# GTI_V5.net
KiCad netlist of a schematic drawn in Altium Designer
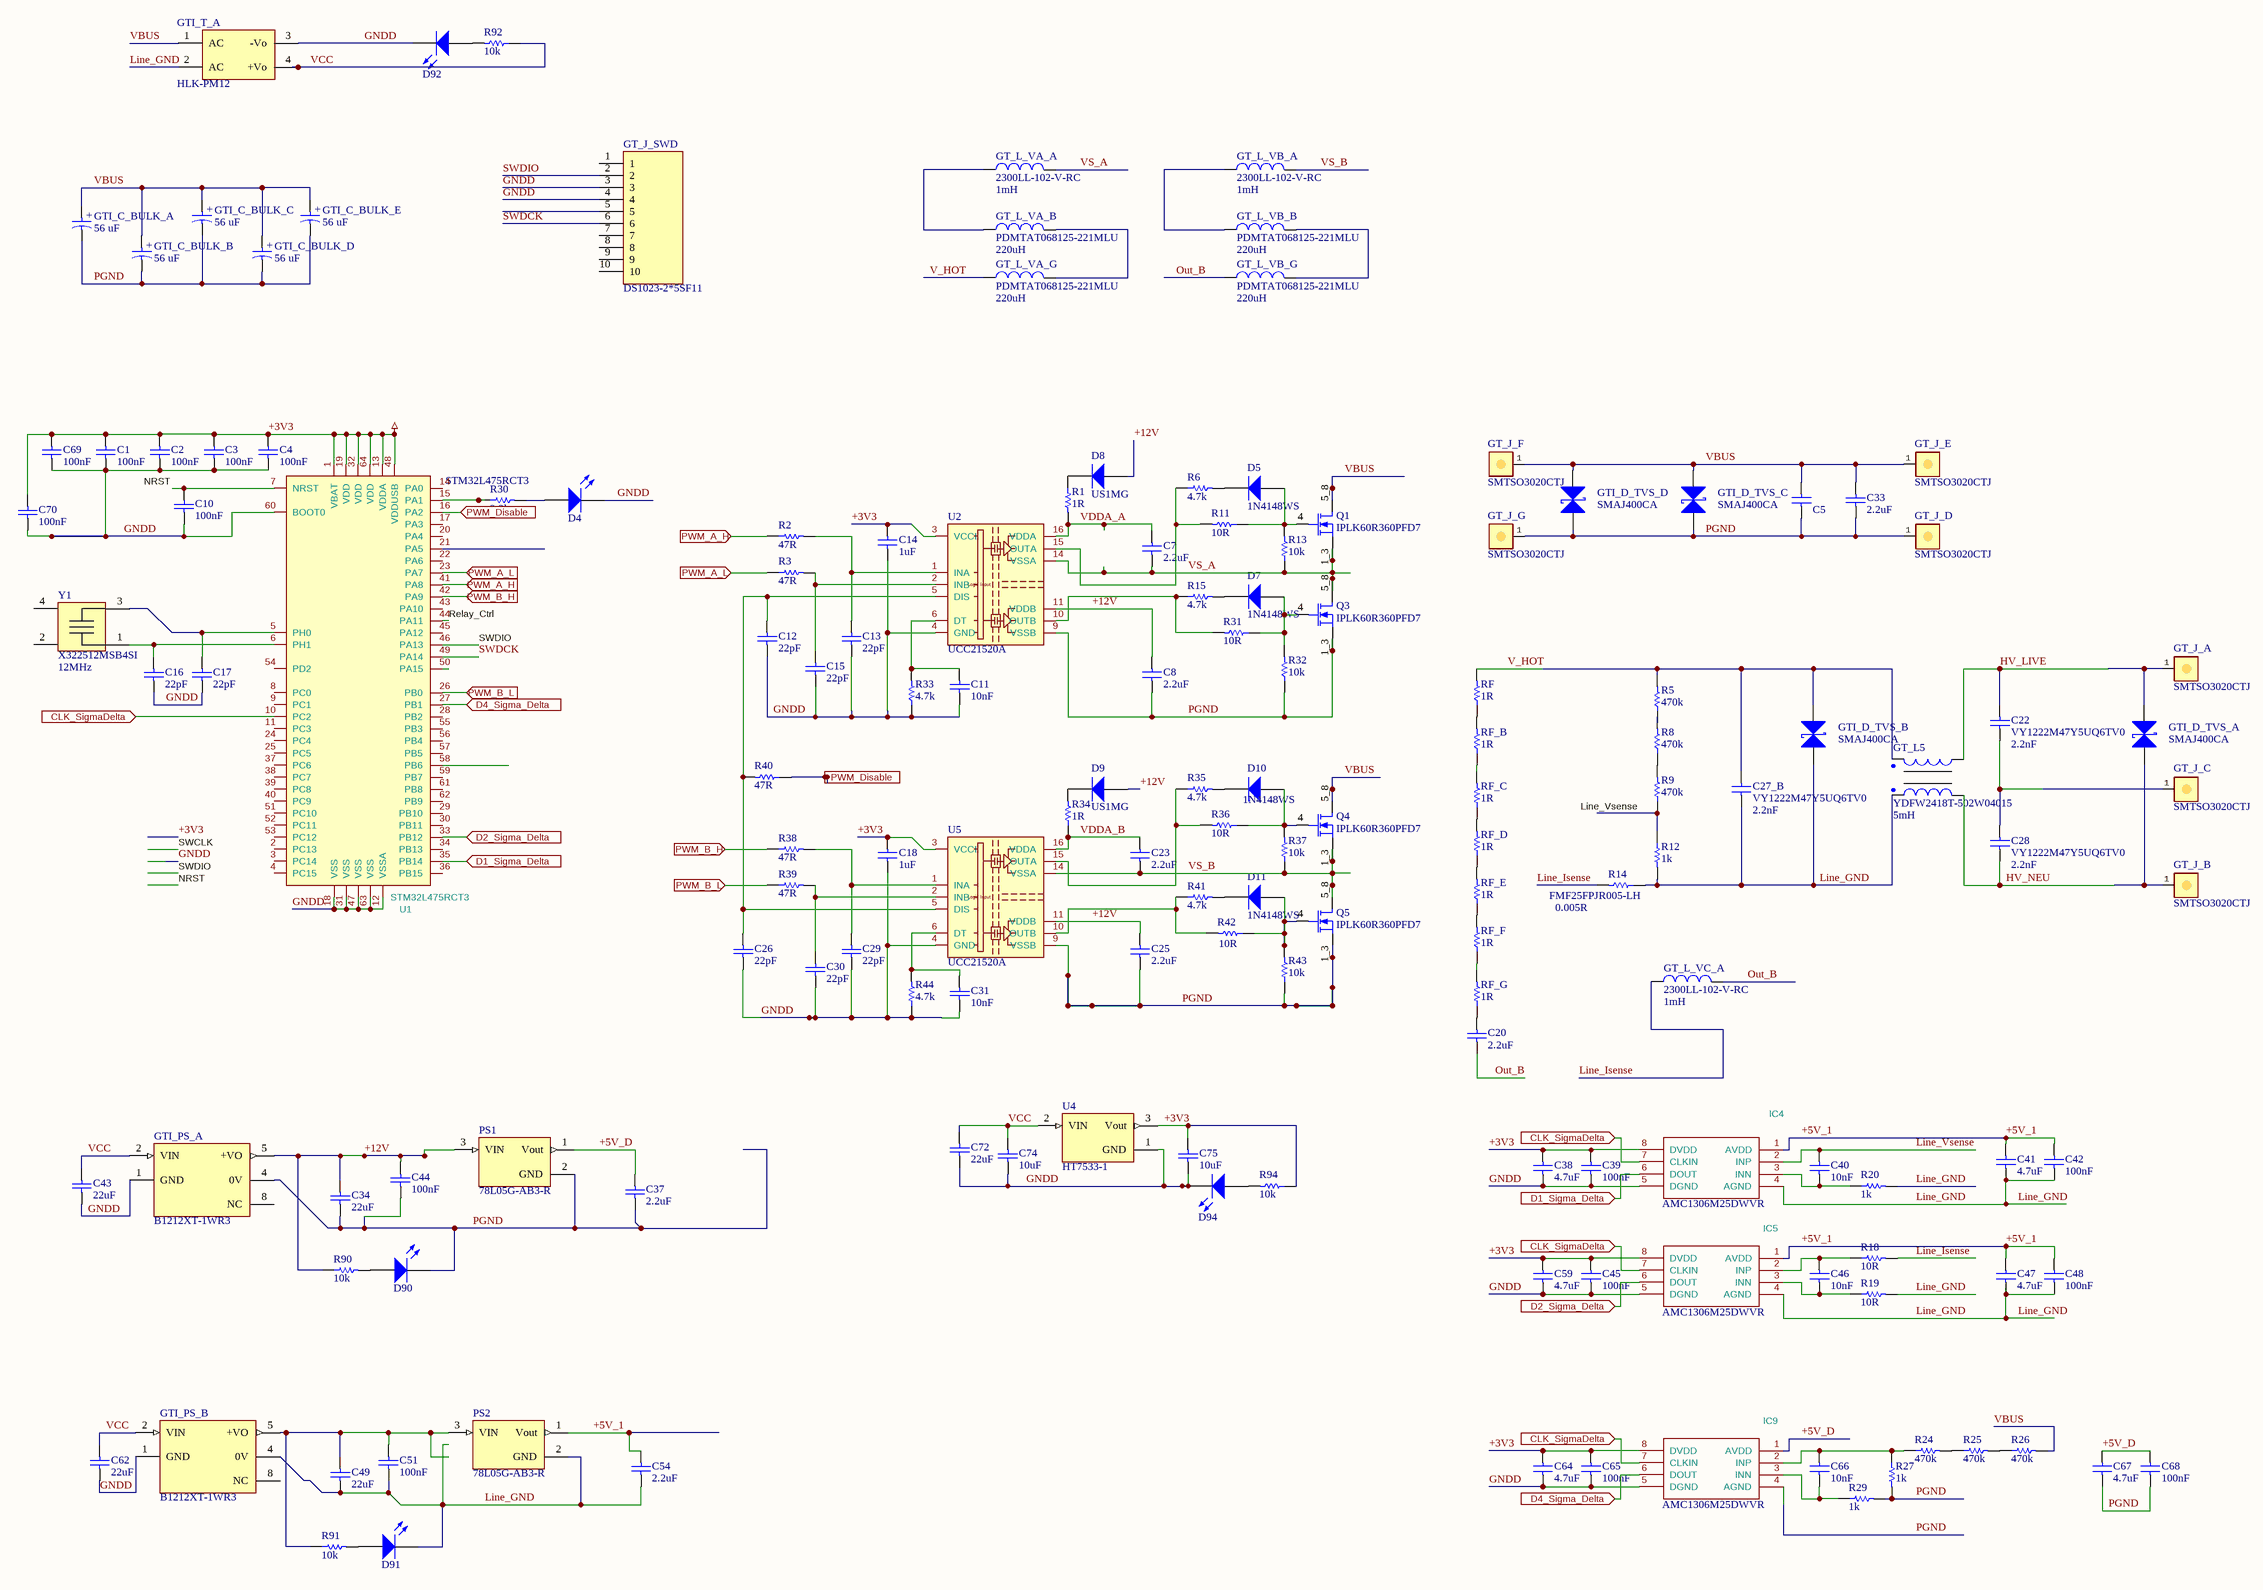
[diagram p0: GTI_V5.SchDoc]

(export (version "E")
  (design (tool "Eeschema 10.0.6"))
  (components
    (comp (ref "C1")
      (value "100nF")
      (footprint "C_0402")
      (description "C - CAPACITOR - MLCC - 100nF - 16V - 0402")
      (fields (field (name "LCSC PART #") "C1525") (field (name "Comment") "CL05B104KO5NNNC"))
      (libsource (lib "JLC_PCB") (part "CL05B104KO5NNNC"))
    )
    (comp (ref "C2")
      (value "100nF")
      (footprint "C_0402")
      (description "C - CAPACITOR - MLCC - 100nF - 16V - 0402")
      (fields (field (name "LCSC PART #") "C1525") (field (name "Comment") "CL05B104KO5NNNC"))
      (libsource (lib "JLC_PCB") (part "CL05B104KO5NNNC"))
    )
    (comp (ref "C3")
      (value "100nF")
      (footprint "C_0402")
      (description "C - CAPACITOR - MLCC - 100nF - 16V - 0402")
      (fields (field (name "LCSC PART #") "C1525") (field (name "Comment") "CL05B104KO5NNNC"))
      (libsource (lib "JLC_PCB") (part "CL05B104KO5NNNC"))
    )
    (comp (ref "C4")
      (value "100nF")
      (footprint "C_0402")
      (description "C - CAPACITOR - MLCC - 100nF - 16V - 0402")
      (fields (field (name "LCSC PART #") "C1525") (field (name "Comment") "CL05B104KO5NNNC"))
      (libsource (lib "JLC_PCB") (part "CL05B104KO5NNNC"))
    )
    (comp (ref "C5")
      (value "C5750X6S2W225KT000N")
      (footprint "C_2220")
      (description "C - CAPACITOR - MLCC - 2.2uF - 450V - 2020")
      (fields (field (name "LCSC PART #") "C445674"))
      (libsource (lib "JLC_PCB") (part "C5750X6S2W225KT000N"))
    )
    (comp (ref "C7")
      (value "2.2uF")
      (footprint "C_0603")
      (description "C - CAPACITOR - MLCC - 2.2uF - 16V - 0603")
      (fields (field (name "LCSC PART #") "C23630") (field (name "Comment") "CL10A225KO8NNNC"))
      (libsource (lib "JLC_PCB") (part "CL10A225KO8NNNC"))
    )
    (comp (ref "C8")
      (value "2.2uF")
      (footprint "C_0603")
      (description "C - CAPACITOR - MLCC - 2.2uF - 16V - 0603")
      (fields (field (name "LCSC PART #") "C23630") (field (name "Comment") "CL10A225KO8NNNC"))
      (libsource (lib "JLC_PCB") (part "CL10A225KO8NNNC"))
    )
    (comp (ref "C10")
      (value "100nF")
      (footprint "C_0402")
      (description "C - CAPACITOR - MLCC - 100nF - 16V - 0402")
      (fields (field (name "LCSC PART #") "C1525") (field (name "Comment") "CL05B104KO5NNNC"))
      (libsource (lib "JLC_PCB") (part "CL05B104KO5NNNC"))
    )
    (comp (ref "C11")
      (value "10nF")
      (footprint "C_0402")
      (description "C - CAPACITOR - MLCC - 10nF - 50V - 0402")
      (fields (field (name "LCSC PART #") "C15195") (field (name "Comment") "CL05B103KB5NNNC"))
      (libsource (lib "JLC_PCB") (part "CL05B103KB5NNNC"))
    )
    (comp (ref "C12")
      (value "22pF")
      (footprint "C_0402")
      (description "C - CAPACITOR - MLCC - 22pF - 50V - 0402")
      (fields (field (name "LCSC PART #") "C1555") (field (name "Comment") "0402CG220J500NT"))
      (libsource (lib "JLC_PCB") (part "0402CG220J500NT"))
    )
    (comp (ref "C13")
      (value "22pF")
      (footprint "C_0402")
      (description "C - CAPACITOR - MLCC - 22pF - 50V - 0402")
      (fields (field (name "LCSC PART #") "C1555") (field (name "Comment") "0402CG220J500NT"))
      (libsource (lib "JLC_PCB") (part "0402CG220J500NT"))
    )
    (comp (ref "C14")
      (value "1uF")
      (footprint "C_0402")
      (description "C - CAPACITOR - MLCC - 1uF - 25V - 0402")
      (fields (field (name "LCSC PART #") "C52923") (field (name "Comment") "CL05A105KA5NQNC"))
      (libsource (lib "JLC_PCB") (part "CL05A105KA5NQNC"))
    )
    (comp (ref "C15")
      (value "22pF")
      (footprint "C_0402")
      (description "C - CAPACITOR - MLCC - 22pF - 50V - 0402")
      (fields (field (name "LCSC PART #") "C1555") (field (name "Comment") "0402CG220J500NT"))
      (libsource (lib "JLC_PCB") (part "0402CG220J500NT"))
    )
    (comp (ref "C16")
      (value "22pF")
      (footprint "C_0402")
      (description "C - CAPACITOR - MLCC - 22pF - 50V - 0402")
      (fields (field (name "LCSC PART #") "C1555") (field (name "Comment") "0402CG220J500NT"))
      (libsource (lib "JLC_PCB") (part "0402CG220J500NT"))
    )
    (comp (ref "C17")
      (value "22pF")
      (footprint "C_0402")
      (description "C - CAPACITOR - MLCC - 22pF - 50V - 0402")
      (fields (field (name "LCSC PART #") "C1555") (field (name "Comment") "0402CG220J500NT"))
      (libsource (lib "JLC_PCB") (part "0402CG220J500NT"))
    )
    (comp (ref "C18")
      (value "1uF")
      (footprint "C_0402")
      (description "C - CAPACITOR - MLCC - 1uF - 25V - 0402")
      (fields (field (name "LCSC PART #") "C52923") (field (name "Comment") "CL05A105KA5NQNC"))
      (libsource (lib "JLC_PCB") (part "CL05A105KA5NQNC"))
    )
    (comp (ref "C20")
      (value "2.2uF")
      (footprint "C_FILM_D27.5")
      (description "C - CAPACITOR - FILM - 2.2uF - 630V - 10mm Plugin")
      (fields (field (name "LCSC PART #") "C5371183") (field (name "Comment") "KP225J2J2705"))
      (libsource (lib "JLC_PCB") (part "KP225J2J2705"))
    )
    (comp (ref "C22")
      (value "VY1222M47Y5UQ6TV0")
      (footprint "C_DISK_D10")
      (description "C - CAPACITOR - X/Y - 2.2nF - 1.5kV - 10mm Plugin")
      (fields (field (name "ALTIUM_VALUE") "2.2nF") (field (name "LCSC PART #") "C499511"))
      (libsource (lib "JLC_PCB") (part "VY1222M47Y5UQ6TV0"))
    )
    (comp (ref "C23")
      (value "2.2uF")
      (footprint "C_0603")
      (description "C - CAPACITOR - MLCC - 2.2uF - 16V - 0603")
      (fields (field (name "LCSC PART #") "C23630") (field (name "Comment") "CL10A225KO8NNNC"))
      (libsource (lib "JLC_PCB") (part "CL10A225KO8NNNC"))
    )
    (comp (ref "C25")
      (value "2.2uF")
      (footprint "C_0603")
      (description "C - CAPACITOR - MLCC - 2.2uF - 16V - 0603")
      (fields (field (name "LCSC PART #") "C23630") (field (name "Comment") "CL10A225KO8NNNC"))
      (libsource (lib "JLC_PCB") (part "CL10A225KO8NNNC"))
    )
    (comp (ref "C26")
      (value "22pF")
      (footprint "C_0402")
      (description "C - CAPACITOR - MLCC - 22pF - 50V - 0402")
      (fields (field (name "LCSC PART #") "C1555") (field (name "Comment") "0402CG220J500NT"))
      (libsource (lib "JLC_PCB") (part "0402CG220J500NT"))
    )
    (comp (ref "C27_B")
      (value "VY1222M47Y5UQ6TV0")
      (footprint "C_DISK_D10")
      (description "C - CAPACITOR - X/Y - 2.2nF - 1.5kV - 10mm Plugin")
      (fields (field (name "ALTIUM_VALUE") "2.2nF") (field (name "LCSC PART #") "C499511"))
      (libsource (lib "JLC_PCB") (part "VY1222M47Y5UQ6TV0"))
    )
    (comp (ref "C28")
      (value "VY1222M47Y5UQ6TV0")
      (footprint "C_DISK_D10")
      (description "C - CAPACITOR - X/Y - 2.2nF - 1.5kV - 10mm Plugin")
      (fields (field (name "ALTIUM_VALUE") "2.2nF") (field (name "LCSC PART #") "C499511"))
      (libsource (lib "JLC_PCB") (part "VY1222M47Y5UQ6TV0"))
    )
    (comp (ref "C29")
      (value "22pF")
      (footprint "C_0402")
      (description "C - CAPACITOR - MLCC - 22pF - 50V - 0402")
      (fields (field (name "LCSC PART #") "C1555") (field (name "Comment") "0402CG220J500NT"))
      (libsource (lib "JLC_PCB") (part "0402CG220J500NT"))
    )
    (comp (ref "C30")
      (value "22pF")
      (footprint "C_0402")
      (description "C - CAPACITOR - MLCC - 22pF - 50V - 0402")
      (fields (field (name "LCSC PART #") "C1555") (field (name "Comment") "0402CG220J500NT"))
      (libsource (lib "JLC_PCB") (part "0402CG220J500NT"))
    )
    (comp (ref "C31")
      (value "10nF")
      (footprint "C_0402")
      (description "C - CAPACITOR - MLCC - 10nF - 50V - 0402")
      (fields (field (name "LCSC PART #") "C15195") (field (name "Comment") "CL05B103KB5NNNC"))
      (libsource (lib "JLC_PCB") (part "CL05B103KB5NNNC"))
    )
    (comp (ref "C33")
      (value "2.2uF")
      (footprint "C_FILM_D27.5")
      (description "C - CAPACITOR - FILM - 2.2uF - 630V - 10mm Plugin")
      (fields (field (name "LCSC PART #") "C5371183") (field (name "Comment") "KP225J2J2705"))
      (libsource (lib "JLC_PCB") (part "KP225J2J2705"))
    )
    (comp (ref "C34")
      (value "22uF")
      (footprint "C_1206")
      (description "C - CAPACITOR - MLCC - 22uF - 25V - 1206")
      (fields (field (name "LCSC PART #") "C12891") (field (name "Comment") "CL31A226KAHNNNE"))
      (libsource (lib "JLC_PCB") (part "CL31A226KAHNNNE"))
    )
    (comp (ref "C37")
      (value "2.2uF")
      (footprint "C_0603")
      (description "C - CAPACITOR - MLCC - 2.2uF - 16V - 0603")
      (fields (field (name "LCSC PART #") "C23630") (field (name "Comment") "CL10A225KO8NNNC"))
      (libsource (lib "JLC_PCB") (part "CL10A225KO8NNNC"))
    )
    (comp (ref "C38")
      (value "4.7uF")
      (footprint "C_0402")
      (description "C - CAPACITOR - MLCC - 4.7uF - 10V - 0402")
      (fields (field (name "LCSC PART #") "C23733") (field (name "Comment") "CL05A475MP5NRNC"))
      (libsource (lib "JLC_PCB") (part "CL05A475MP5NRNC"))
    )
    (comp (ref "C39")
      (value "100nF")
      (footprint "C_0402")
      (description "C - CAPACITOR - MLCC - 100nF - 16V - 0402")
      (fields (field (name "LCSC PART #") "C1525") (field (name "Comment") "CL05B104KO5NNNC"))
      (libsource (lib "JLC_PCB") (part "CL05B104KO5NNNC"))
    )
    (comp (ref "C40")
      (value "10nF")
      (footprint "C_0402")
      (description "C - CAPACITOR - MLCC - 10nF - 50V - 0402")
      (fields (field (name "LCSC PART #") "C15195") (field (name "Comment") "CL05B103KB5NNNC"))
      (libsource (lib "JLC_PCB") (part "CL05B103KB5NNNC"))
    )
    (comp (ref "C41")
      (value "4.7uF")
      (footprint "C_0402")
      (description "C - CAPACITOR - MLCC - 4.7uF - 10V - 0402")
      (fields (field (name "LCSC PART #") "C23733") (field (name "Comment") "CL05A475MP5NRNC"))
      (libsource (lib "JLC_PCB") (part "CL05A475MP5NRNC"))
    )
    (comp (ref "C42")
      (value "100nF")
      (footprint "C_0402")
      (description "C - CAPACITOR - MLCC - 100nF - 16V - 0402")
      (fields (field (name "LCSC PART #") "C1525") (field (name "Comment") "CL05B104KO5NNNC"))
      (libsource (lib "JLC_PCB") (part "CL05B104KO5NNNC"))
    )
    (comp (ref "C43")
      (value "22uF")
      (footprint "C_1206")
      (description "C - CAPACITOR - MLCC - 22uF - 25V - 1206")
      (fields (field (name "LCSC PART #") "C12891") (field (name "Comment") "CL31A226KAHNNNE"))
      (libsource (lib "JLC_PCB") (part "CL31A226KAHNNNE"))
    )
    (comp (ref "C44")
      (value "100nF")
      (footprint "C_0603")
      (description "C - CAPACITOR - MLCC - 100nF - 50V - 0603")
      (fields (field (name "LCSC PART #") "C14663") (field (name "Comment") "CC0603KRX7R9BB104"))
      (libsource (lib "JLC_PCB") (part "CC0603KRX7R9BB104"))
    )
    (comp (ref "C45")
      (value "100nF")
      (footprint "C_0402")
      (description "C - CAPACITOR - MLCC - 100nF - 16V - 0402")
      (fields (field (name "LCSC PART #") "C1525") (field (name "Comment") "CL05B104KO5NNNC"))
      (libsource (lib "JLC_PCB") (part "CL05B104KO5NNNC"))
    )
    (comp (ref "C46")
      (value "10nF")
      (footprint "C_0402")
      (description "C - CAPACITOR - MLCC - 10nF - 50V - 0402")
      (fields (field (name "LCSC PART #") "C15195") (field (name "Comment") "CL05B103KB5NNNC"))
      (libsource (lib "JLC_PCB") (part "CL05B103KB5NNNC"))
    )
    (comp (ref "C47")
      (value "4.7uF")
      (footprint "C_0402")
      (description "C - CAPACITOR - MLCC - 4.7uF - 10V - 0402")
      (fields (field (name "LCSC PART #") "C23733") (field (name "Comment") "CL05A475MP5NRNC"))
      (libsource (lib "JLC_PCB") (part "CL05A475MP5NRNC"))
    )
    (comp (ref "C48")
      (value "100nF")
      (footprint "C_0402")
      (description "C - CAPACITOR - MLCC - 100nF - 16V - 0402")
      (fields (field (name "LCSC PART #") "C1525") (field (name "Comment") "CL05B104KO5NNNC"))
      (libsource (lib "JLC_PCB") (part "CL05B104KO5NNNC"))
    )
    (comp (ref "C49")
      (value "22uF")
      (footprint "C_1206")
      (description "C - CAPACITOR - MLCC - 22uF - 25V - 1206")
      (fields (field (name "LCSC PART #") "C12891") (field (name "Comment") "CL31A226KAHNNNE"))
      (libsource (lib "JLC_PCB") (part "CL31A226KAHNNNE"))
    )
    (comp (ref "C51")
      (value "100nF")
      (footprint "C_0603")
      (description "C - CAPACITOR - MLCC - 100nF - 50V - 0603")
      (fields (field (name "LCSC PART #") "C14663") (field (name "Comment") "CC0603KRX7R9BB104"))
      (libsource (lib "JLC_PCB") (part "CC0603KRX7R9BB104"))
    )
    (comp (ref "C54")
      (value "2.2uF")
      (footprint "C_0603")
      (description "C - CAPACITOR - MLCC - 2.2uF - 16V - 0603")
      (fields (field (name "LCSC PART #") "C23630") (field (name "Comment") "CL10A225KO8NNNC"))
      (libsource (lib "JLC_PCB") (part "CL10A225KO8NNNC"))
    )
    (comp (ref "C59")
      (value "4.7uF")
      (footprint "C_0402")
      (description "C - CAPACITOR - MLCC - 4.7uF - 10V - 0402")
      (fields (field (name "LCSC PART #") "C23733") (field (name "Comment") "CL05A475MP5NRNC"))
      (libsource (lib "JLC_PCB") (part "CL05A475MP5NRNC"))
    )
    (comp (ref "C62")
      (value "22uF")
      (footprint "C_1206")
      (description "C - CAPACITOR - MLCC - 22uF - 25V - 1206")
      (fields (field (name "LCSC PART #") "C12891") (field (name "Comment") "CL31A226KAHNNNE"))
      (libsource (lib "JLC_PCB") (part "CL31A226KAHNNNE"))
    )
    (comp (ref "C64")
      (value "4.7uF")
      (footprint "C_0402")
      (description "C - CAPACITOR - MLCC - 4.7uF - 10V - 0402")
      (fields (field (name "LCSC PART #") "C23733") (field (name "Comment") "CL05A475MP5NRNC"))
      (libsource (lib "JLC_PCB") (part "CL05A475MP5NRNC"))
    )
    (comp (ref "C65")
      (value "100nF")
      (footprint "C_0402")
      (description "C - CAPACITOR - MLCC - 100nF - 16V - 0402")
      (fields (field (name "LCSC PART #") "C1525") (field (name "Comment") "CL05B104KO5NNNC"))
      (libsource (lib "JLC_PCB") (part "CL05B104KO5NNNC"))
    )
    (comp (ref "C66")
      (value "10nF")
      (footprint "C_0402")
      (description "C - CAPACITOR - MLCC - 10nF - 50V - 0402")
      (fields (field (name "LCSC PART #") "C15195") (field (name "Comment") "CL05B103KB5NNNC"))
      (libsource (lib "JLC_PCB") (part "CL05B103KB5NNNC"))
    )
    (comp (ref "C67")
      (value "4.7uF")
      (footprint "C_0402")
      (description "C - CAPACITOR - MLCC - 4.7uF - 10V - 0402")
      (fields (field (name "LCSC PART #") "C23733") (field (name "Comment") "CL05A475MP5NRNC"))
      (libsource (lib "JLC_PCB") (part "CL05A475MP5NRNC"))
    )
    (comp (ref "C68")
      (value "100nF")
      (footprint "C_0402")
      (description "C - CAPACITOR - MLCC - 100nF - 16V - 0402")
      (fields (field (name "LCSC PART #") "C1525") (field (name "Comment") "CL05B104KO5NNNC"))
      (libsource (lib "JLC_PCB") (part "CL05B104KO5NNNC"))
    )
    (comp (ref "C69")
      (value "100nF")
      (footprint "C_0402")
      (description "C - CAPACITOR - MLCC - 100nF - 16V - 0402")
      (fields (field (name "LCSC PART #") "C1525") (field (name "Comment") "CL05B104KO5NNNC"))
      (libsource (lib "JLC_PCB") (part "CL05B104KO5NNNC"))
    )
    (comp (ref "C70")
      (value "100nF")
      (footprint "C_0402")
      (description "C - CAPACITOR - MLCC - 100nF - 16V - 0402")
      (fields (field (name "LCSC PART #") "C1525") (field (name "Comment") "CL05B104KO5NNNC"))
      (libsource (lib "JLC_PCB") (part "CL05B104KO5NNNC"))
    )
    (comp (ref "C72")
      (value "22uF")
      (footprint "C_1206")
      (description "C - CAPACITOR - MLCC - 22uF - 25V - 1206")
      (fields (field (name "LCSC PART #") "C12891") (field (name "Comment") "CL31A226KAHNNNE"))
      (libsource (lib "JLC_PCB") (part "CL31A226KAHNNNE"))
    )
    (comp (ref "C74")
      (value "10uF")
      (footprint "C_0603")
      (description "C - CAPACITOR - MLCC - 10uF - 25V - 0603")
      (fields (field (name "LCSC PART #") "C96446") (field (name "Comment") "CL10A106MA8NRNC"))
      (libsource (lib "JLC_PCB") (part "CL10A106MA8NRNC"))
    )
    (comp (ref "C75")
      (value "10uF")
      (footprint "C_0603")
      (description "C - CAPACITOR - MLCC - 10uF - 25V - 0603")
      (fields (field (name "LCSC PART #") "C96446") (field (name "Comment") "CL10A106MA8NRNC"))
      (libsource (lib "JLC_PCB") (part "CL10A106MA8NRNC"))
    )
    (comp (ref "D4")
      (value "KT-0603R")
      (footprint "D_0603")
      (description "D - LED - 0603 - Red")
      (fields (field (name "LCSC PART #") "C2286"))
      (libsource (lib "JLC_PCB") (part "KT-0603R"))
    )
    (comp (ref "D5")
      (value "1N4148WS")
      (footprint "SOD-323")
      (description "D - DIODE - FAST TRR - 100V - 150mA - 4ns")
      (fields (field (name "LCSC PART #") "C2128"))
      (libsource (lib "JLC_PCB") (part "1N4148WS"))
    )
    (comp (ref "D7")
      (value "1N4148WS")
      (footprint "SOD-323")
      (description "D - DIODE - FAST TRR - 100V - 150mA - 4ns")
      (fields (field (name "LCSC PART #") "C2128"))
      (libsource (lib "JLC_PCB") (part "1N4148WS"))
    )
    (comp (ref "D8")
      (value "US1MG")
      (footprint "DO-214AC")
      (description "D - DIODE - FAST TRR - 1KV - 1A")
      (fields (field (name "LCSC PART #") "C412437"))
      (libsource (lib "JLC_PCB") (part "US1MG"))
    )
    (comp (ref "D9")
      (value "US1MG")
      (footprint "DO-214AC")
      (description "D - DIODE - FAST TRR - 1KV - 1A")
      (fields (field (name "LCSC PART #") "C412437"))
      (libsource (lib "JLC_PCB") (part "US1MG"))
    )
    (comp (ref "D10")
      (value "1N4148WS")
      (footprint "SOD-323")
      (description "D - DIODE - FAST TRR - 100V - 150mA - 4ns")
      (fields (field (name "LCSC PART #") "C2128"))
      (libsource (lib "JLC_PCB") (part "1N4148WS"))
    )
    (comp (ref "D11")
      (value "1N4148WS")
      (footprint "SOD-323")
      (description "D - DIODE - FAST TRR - 100V - 150mA - 4ns")
      (fields (field (name "LCSC PART #") "C2128"))
      (libsource (lib "JLC_PCB") (part "1N4148WS"))
    )
    (comp (ref "D90")
      (value "KT-0603R")
      (footprint "D_0603")
      (description "D - LED - 0603 - Red")
      (fields (field (name "LCSC PART #") "C2286"))
      (libsource (lib "JLC_PCB") (part "KT-0603R"))
    )
    (comp (ref "D91")
      (value "KT-0603R")
      (footprint "D_0603")
      (description "D - LED - 0603 - Red")
      (fields (field (name "LCSC PART #") "C2286"))
      (libsource (lib "JLC_PCB") (part "KT-0603R"))
    )
    (comp (ref "D92")
      (value "KT-0603R")
      (footprint "D_0603")
      (description "D - LED - 0603 - Red")
      (fields (field (name "LCSC PART #") "C2286"))
      (libsource (lib "JLC_PCB") (part "KT-0603R"))
    )
    (comp (ref "D94")
      (value "KT-0603R")
      (footprint "D_0603")
      (description "D - LED - 0603 - Red")
      (fields (field (name "LCSC PART #") "C2286"))
      (libsource (lib "JLC_PCB") (part "KT-0603R"))
    )
    (comp (ref "GTI_C_BULK_A")
      (value "56 uF")
      (footprint "CAP_D18_L7.5")
      (description "C - CAPACITOR - ELECTROYLTIC - 56 uF - 450V - TH")
      (fields (field (name "MANUFACTURER") "AISHI (AIHUA) GROUP") (field (name "LCSC PART #") "C2902571"))
      (libsource (lib "JLC_PCB") (part "EGW2WM560M25OT"))
    )
    (comp (ref "GTI_C_BULK_B")
      (value "56 uF")
      (footprint "CAP_D18_L7.5")
      (description "C - CAPACITOR - ELECTROYLTIC - 56 uF - 450V - TH")
      (fields (field (name "MANUFACTURER") "AISHI (AIHUA) GROUP") (field (name "LCSC PART #") "C2902571"))
      (libsource (lib "JLC_PCB") (part "EGW2WM560M25OT"))
    )
    (comp (ref "GTI_C_BULK_C")
      (value "56 uF")
      (footprint "CAP_D18_L7.5")
      (description "C - CAPACITOR - ELECTROYLTIC - 56 uF - 450V - TH")
      (fields (field (name "MANUFACTURER") "AISHI (AIHUA) GROUP") (field (name "LCSC PART #") "C2902571"))
      (libsource (lib "JLC_PCB") (part "EGW2WM560M25OT"))
    )
    (comp (ref "GTI_C_BULK_D")
      (value "56 uF")
      (footprint "CAP_D18_L7.5")
      (description "C - CAPACITOR - ELECTROYLTIC - 56 uF - 450V - TH")
      (fields (field (name "MANUFACTURER") "AISHI (AIHUA) GROUP") (field (name "LCSC PART #") "C2902571"))
      (libsource (lib "JLC_PCB") (part "EGW2WM560M25OT"))
    )
    (comp (ref "GTI_C_BULK_E")
      (value "56 uF")
      (footprint "CAP_D18_L7.5")
      (description "C - CAPACITOR - ELECTROYLTIC - 56 uF - 450V - TH")
      (fields (field (name "MANUFACTURER") "AISHI (AIHUA) GROUP") (field (name "LCSC PART #") "C2902571"))
      (libsource (lib "JLC_PCB") (part "EGW2WM560M25OT"))
    )
    (comp (ref "GTI_D_TVS_A")
      (value "SMAJ400CA")
      (footprint "DO-214AC")
      (description "D - DIODE - TVS - 400V - 0.7A")
      (fields (field (name "LCSC PART #") "C132232"))
      (libsource (lib "JLC_PCB") (part "SMAJ400CA"))
    )
    (comp (ref "GTI_D_TVS_B")
      (value "SMAJ400CA")
      (footprint "DO-214AC")
      (description "D - DIODE - TVS - 400V - 0.7A")
      (fields (field (name "LCSC PART #") "C132232"))
      (libsource (lib "JLC_PCB") (part "SMAJ400CA"))
    )
    (comp (ref "GTI_D_TVS_C")
      (value "SMAJ400CA")
      (footprint "DO-214AC")
      (description "D - DIODE - TVS - 400V - 0.7A")
      (fields (field (name "LCSC PART #") "C132232"))
      (libsource (lib "JLC_PCB") (part "SMAJ400CA"))
    )
    (comp (ref "GTI_D_TVS_D")
      (value "SMAJ400CA")
      (footprint "DO-214AC")
      (description "D - DIODE - TVS - 400V - 0.7A")
      (fields (field (name "LCSC PART #") "C132232"))
      (libsource (lib "JLC_PCB") (part "SMAJ400CA"))
    )
    (comp (ref "GTI_PS_A")
      (value "B1212XT-1WR3")
      (footprint "CONV_B0512XT-1WR3")
      (description "T - Isolated Module DC DC Converter 12 -> 12V 84mA - DIP")
      (fields (field (name "LCSC PART #") "C2684910") (field (name "MF") "MORNSUN"))
      (libsource (lib "JLC_PCB") (part "B1212XT-1WR3"))
    )
    (comp (ref "GTI_PS_B")
      (value "B1212XT-1WR3")
      (footprint "CONV_B0512XT-1WR3")
      (description "T - Isolated Module DC DC Converter 12 -> 12V 84mA - DIP")
      (fields (field (name "LCSC PART #") "C2684910") (field (name "MF") "MORNSUN"))
      (libsource (lib "JLC_PCB") (part "B1212XT-1WR3"))
    )
    (comp (ref "GTI_T_A")
      (value "HLK-PM12")
      (footprint "HLK-PM12")
      (description "T - 12V - 0.25A - OFF LINE PSU")
      (fields (field (name "MF") "HI-LINK") (field (name "LCSC PART #") "C209905"))
      (libsource (lib "JLC_PCB") (part "HLK-PM12"))
    )
    (comp (ref "GT_J_A")
      (value "SMTSO3020CTJ")
      (footprint "SMTSO3020CTJ")
      (description "J - PCB NUT - M3 x 2")
      (fields (field (name "LCSC PART #") "C2916381"))
      (libsource (lib "JLC_PCB") (part "SMTSO3020CTJ"))
    )
    (comp (ref "GT_J_B")
      (value "SMTSO3020CTJ")
      (footprint "SMTSO3020CTJ")
      (description "J - PCB NUT - M3 x 2")
      (fields (field (name "LCSC PART #") "C2916381"))
      (libsource (lib "JLC_PCB") (part "SMTSO3020CTJ"))
    )
    (comp (ref "GT_J_C")
      (value "SMTSO3020CTJ")
      (footprint "SMTSO3020CTJ")
      (description "J - PCB NUT - M3 x 2")
      (fields (field (name "LCSC PART #") "C2916381"))
      (libsource (lib "JLC_PCB") (part "SMTSO3020CTJ"))
    )
    (comp (ref "GT_J_D")
      (value "SMTSO3020CTJ")
      (footprint "SMTSO3020CTJ")
      (description "J - PCB NUT - M3 x 2")
      (fields (field (name "LCSC PART #") "C2916381"))
      (libsource (lib "JLC_PCB") (part "SMTSO3020CTJ"))
    )
    (comp (ref "GT_J_E")
      (value "SMTSO3020CTJ")
      (footprint "SMTSO3020CTJ")
      (description "J - PCB NUT - M3 x 2")
      (fields (field (name "LCSC PART #") "C2916381"))
      (libsource (lib "JLC_PCB") (part "SMTSO3020CTJ"))
    )
    (comp (ref "GT_J_F")
      (value "SMTSO3020CTJ")
      (footprint "SMTSO3020CTJ")
      (description "J - PCB NUT - M3 x 2")
      (fields (field (name "LCSC PART #") "C2916381"))
      (libsource (lib "") (part "SMTSO3020CTJ_1"))
    )
    (comp (ref "GT_J_G")
      (value "SMTSO3020CTJ")
      (footprint "SMTSO3020CTJ")
      (description "J - PCB NUT - M3 x 2")
      (fields (field (name "LCSC PART #") "C2916381"))
      (libsource (lib "") (part "SMTSO3020CTJ_1"))
    )
    (comp (ref "GT_J_SWD")
      (value "DS1023-2*5SF11")
      (footprint "HDR_FEM_2X5P")
      (description "J - JACK - PIN_HEADER 2X5P")
      (fields (field (name "LCSC PART #") "C92270"))
      (libsource (lib "JLC_PCB") (part "DS1023-2*5SF11"))
    )
    (comp (ref "GT_L5")
      (value "YDFW2418T-502W04015")
      (footprint "YDFW2418T-103W03015")
      (description "L - CM CHOKE - 5mH")
      (fields (field (name "LCSC PART #") "C5563765") (field (name "ALTIUM_VALUE") "5mH"))
      (libsource (lib "JLC_PCB") (part "YDFW2418T-502W04015"))
    )
    (comp (ref "GT_L_VA_A")
      (value "2300LL-102-V-RC")
      (footprint "IND_2300LL-102-V-RC")
      (description "L - INDUCTOR - 1mH - 3.5A - TOROID")
      (fields (field (name "LCSC PART #") "C17539870") (field (name "ALTIUM_VALUE") "1mH"))
      (libsource (lib "JLC_PCB") (part "2300LL-102-V-RC"))
    )
    (comp (ref "GT_L_VA_B")
      (value "PDMTAT068125-221MLU")
      (footprint "L_TOROID_8MM_D")
      (description "L - INDUCTOR - 220uH - 5A - 23mm")
      (fields (field (name "LCSC PART #") "C3011545") (field (name "ALTIUM_VALUE") "220uH"))
      (libsource (lib "JLC_PCB") (part "PDMTAT068125-221MLU"))
    )
    (comp (ref "GT_L_VA_G")
      (value "PDMTAT068125-221MLU")
      (footprint "L_TOROID_8MM_D")
      (description "L - INDUCTOR - 220uH - 5A - 23mm")
      (fields (field (name "LCSC PART #") "C3011545") (field (name "ALTIUM_VALUE") "220uH"))
      (libsource (lib "JLC_PCB") (part "PDMTAT068125-221MLU"))
    )
    (comp (ref "GT_L_VB_A")
      (value "2300LL-102-V-RC")
      (footprint "IND_2300LL-102-V-RC")
      (description "L - INDUCTOR - 1mH - 3.5A - TOROID")
      (fields (field (name "LCSC PART #") "C17539870") (field (name "ALTIUM_VALUE") "1mH"))
      (libsource (lib "JLC_PCB") (part "2300LL-102-V-RC"))
    )
    (comp (ref "GT_L_VB_B")
      (value "PDMTAT068125-221MLU")
      (footprint "L_TOROID_8MM_D")
      (description "L - INDUCTOR - 220uH - 5A - 23mm")
      (fields (field (name "LCSC PART #") "C3011545") (field (name "ALTIUM_VALUE") "220uH"))
      (libsource (lib "JLC_PCB") (part "PDMTAT068125-221MLU"))
    )
    (comp (ref "GT_L_VB_G")
      (value "PDMTAT068125-221MLU")
      (footprint "L_TOROID_8MM_D")
      (description "L - INDUCTOR - 220uH - 5A - 23mm")
      (fields (field (name "LCSC PART #") "C3011545") (field (name "ALTIUM_VALUE") "220uH"))
      (libsource (lib "JLC_PCB") (part "PDMTAT068125-221MLU"))
    )
    (comp (ref "GT_L_VC_A")
      (value "2300LL-102-V-RC")
      (footprint "IND_2300LL-102-V-RC")
      (description "L - INDUCTOR - 1mH - 3.5A - TOROID")
      (fields (field (name "LCSC PART #") "C17539870") (field (name "ALTIUM_VALUE") "1mH"))
      (libsource (lib "JLC_PCB") (part "2300LL-102-V-RC"))
    )
    (comp (ref "IC4")
      (value "AMC1306M25DWVR")
      (footprint "SOIC-8-P1.27-W7.5")
      (description "U - IC - SPECIALIZED ADC")
      (fields
        (field (name "MOUSER PART NUMBER") "595-MC1306M25QDWVRQ1")
        (field (name "MANUFACTURER_PART_NUMBER") "AMC1306M25QDWVRQ1")
      )
      (libsource (lib "JLC_PCB") (part "AMC1306M25DWVR"))
    )
    (comp (ref "IC5")
      (value "AMC1306M25DWVR")
      (footprint "SOIC-8-P1.27-W7.5")
      (description "U - IC - SPECIALIZED ADC")
      (fields
        (field (name "MOUSER PART NUMBER") "595-MC1306M25QDWVRQ1")
        (field (name "MANUFACTURER_PART_NUMBER") "AMC1306M25QDWVRQ1")
      )
      (libsource (lib "JLC_PCB") (part "AMC1306M25DWVR"))
    )
    (comp (ref "IC9")
      (value "AMC1306M25DWVR")
      (footprint "SOIC-8-P1.27-W7.5")
      (description "U - IC - SPECIALIZED ADC")
      (fields
        (field (name "MOUSER PART NUMBER") "595-MC1306M25QDWVRQ1")
        (field (name "MANUFACTURER_PART_NUMBER") "AMC1306M25QDWVRQ1")
      )
      (libsource (lib "JLC_PCB") (part "AMC1306M25DWVR"))
    )
    (comp (ref "PS1")
      (value "78L05G-AB3-R")
      (footprint "SOT-223-3")
      (description "U - IC - 5V Power Regulator")
      (fields (field (name "LCSC PART #") "C71136"))
      (libsource (lib "JLC_PCB") (part "78L05G-AB3-R"))
    )
    (comp (ref "PS2")
      (value "78L05G-AB3-R")
      (footprint "SOT-223-3")
      (description "U - IC - 5V Power Regulator")
      (fields (field (name "LCSC PART #") "C71136"))
      (libsource (lib "JLC_PCB") (part "78L05G-AB3-R"))
    )
    (comp (ref "Q1")
      (value "IPLK60R360PFD7")
      (footprint "SO-8FL")
      (description "Q - TRANSISTOR - MOSFET (N) - 600V - 303m - 13A")
      (fields (field (name "LCSC PART #") "C537054"))
      (libsource (lib "JLC_PCB") (part "IPLK60R360PFD7"))
    )
    (comp (ref "Q3")
      (value "IPLK60R360PFD7")
      (footprint "SO-8FL")
      (description "Q - TRANSISTOR - MOSFET (N) - 600V - 303m - 13A")
      (fields (field (name "LCSC PART #") "C537054"))
      (libsource (lib "JLC_PCB") (part "IPLK60R360PFD7"))
    )
    (comp (ref "Q4")
      (value "IPLK60R360PFD7")
      (footprint "SO-8FL")
      (description "Q - TRANSISTOR - MOSFET (N) - 600V - 303m - 13A")
      (fields (field (name "LCSC PART #") "C537054"))
      (libsource (lib "JLC_PCB") (part "IPLK60R360PFD7"))
    )
    (comp (ref "Q5")
      (value "IPLK60R360PFD7")
      (footprint "SO-8FL")
      (description "Q - TRANSISTOR - MOSFET (N) - 600V - 303m - 13A")
      (fields (field (name "LCSC PART #") "C537054"))
      (libsource (lib "JLC_PCB") (part "IPLK60R360PFD7"))
    )
    (comp (ref "R1")
      (value "1R")
      (footprint "R_0603")
      (description "R - RESISTOR - SMD - 1R - 1% -  0603")
      (fields (field (name "LCSC PART #") "C22936") (field (name "Comment") "0603WAF100KT5E"))
      (libsource (lib "JLC_PCB") (part "0603WAF100KT5E"))
    )
    (comp (ref "R2")
      (value "47R")
      (footprint "R_0402")
      (description "R - RESISTOR - SMD - 47R - 1% - 0402")
      (fields (field (name "LCSC PART #") "C25118") (field (name "Comment") "0402WGF470JTCE"))
      (libsource (lib "JLC_PCB") (part "0402WGF470JTCE"))
    )
    (comp (ref "R3")
      (value "47R")
      (footprint "R_0402")
      (description "R - RESISTOR - SMD - 47R - 1% - 0402")
      (fields (field (name "LCSC PART #") "C25118") (field (name "Comment") "0402WGF470JTCE"))
      (libsource (lib "JLC_PCB") (part "0402WGF470JTCE"))
    )
    (comp (ref "R5")
      (value "470k")
      (footprint "R_0805")
      (description "R - RESISTOR - SMD - 470k - 1% - 0805")
      (fields (field (name "LCSC PART #") "C17709") (field (name "Comment") "0805W8F4703T5E"))
      (libsource (lib "JLC_PCB") (part "0805W8F4703T5E"))
    )
    (comp (ref "R6")
      (value "4.7k")
      (footprint "R_0402")
      (description "R - RESISTOR - SMD - 4.7k - 1% - 0402")
      (fields (field (name "LCSC PART #") "C25900") (field (name "Comment") "0402WGF4701TCE"))
      (libsource (lib "JLC_PCB") (part "0402WGF4701TCE"))
    )
    (comp (ref "R8")
      (value "470k")
      (footprint "R_0805")
      (description "R - RESISTOR - SMD - 470k - 1% - 0805")
      (fields (field (name "LCSC PART #") "C17709") (field (name "Comment") "0805W8F4703T5E"))
      (libsource (lib "JLC_PCB") (part "0805W8F4703T5E"))
    )
    (comp (ref "R9")
      (value "470k")
      (footprint "R_0805")
      (description "R - RESISTOR - SMD - 470k - 1% - 0805")
      (fields (field (name "LCSC PART #") "C17709") (field (name "Comment") "0805W8F4703T5E"))
      (libsource (lib "JLC_PCB") (part "0805W8F4703T5E"))
    )
    (comp (ref "R11")
      (value "10R")
      (footprint "R_0603")
      (description "R - RESISTOR - SMD - 10R - 1% - 0603")
      (fields (field (name "LCSC PART #") "C22859") (field (name "Comment") "0603WAF100JT5E"))
      (libsource (lib "JLC_PCB") (part "0603WAF100JT5E"))
    )
    (comp (ref "R12")
      (value "1k")
      (footprint "R_0402")
      (description "R - RESISTOR - SMD - 1k - 1% - 0402")
      (fields (field (name "LCSC PART #") "C11702") (field (name "Comment") "0402WGF1001TCE"))
      (libsource (lib "JLC_PCB") (part "0402WGF1001TCE"))
    )
    (comp (ref "R13")
      (value "10k")
      (footprint "R_0402")
      (description "R - RESISTOR - SMD - 10k - 1% - 0402")
      (fields (field (name "LCSC PART #") "C25744") (field (name "Comment") "0402WGF1002TCE"))
      (libsource (lib "JLC_PCB") (part "0402WGF1002TCE"))
    )
    (comp (ref "R14")
      (value "FMF25FPJR005-LH")
      (footprint "R_2512")
      (description "R - RESISTOR - SMD - 0.005R - 1% - 2512 - 2W")
      (fields (field (name "ALTIUM_VALUE") "0.005R") (field (name "LCSC PART #") "C371096"))
      (libsource (lib "JLC_PCB") (part "FMF25FPJR005-LH"))
    )
    (comp (ref "R15")
      (value "4.7k")
      (footprint "R_0402")
      (description "R - RESISTOR - SMD - 4.7k - 1% - 0402")
      (fields (field (name "LCSC PART #") "C25900") (field (name "Comment") "0402WGF4701TCE"))
      (libsource (lib "JLC_PCB") (part "0402WGF4701TCE"))
    )
    (comp (ref "R18")
      (value "10R")
      (footprint "R_0402")
      (description "R - RESISTOR - SMD - 10R - 1% - 0402")
      (fields (field (name "LCSC PART #") "C25077") (field (name "Comment") "0402WGF100JTCE"))
      (libsource (lib "JLC_PCB") (part "0402WGF100JTCE"))
    )
    (comp (ref "R19")
      (value "10R")
      (footprint "R_0402")
      (description "R - RESISTOR - SMD - 10R - 1% - 0402")
      (fields (field (name "LCSC PART #") "C25077") (field (name "Comment") "0402WGF100JTCE"))
      (libsource (lib "JLC_PCB") (part "0402WGF100JTCE"))
    )
    (comp (ref "R20")
      (value "1k")
      (footprint "R_0402")
      (description "R - RESISTOR - SMD - 1k - 1% - 0402")
      (fields (field (name "LCSC PART #") "C11702") (field (name "Comment") "0402WGF1001TCE"))
      (libsource (lib "JLC_PCB") (part "0402WGF1001TCE"))
    )
    (comp (ref "R24")
      (value "470k")
      (footprint "R_0805")
      (description "R - RESISTOR - SMD - 470k - 1% - 0805")
      (fields (field (name "LCSC PART #") "C17709") (field (name "Comment") "0805W8F4703T5E"))
      (libsource (lib "JLC_PCB") (part "0805W8F4703T5E"))
    )
    (comp (ref "R25")
      (value "470k")
      (footprint "R_0805")
      (description "R - RESISTOR - SMD - 470k - 1% - 0805")
      (fields (field (name "LCSC PART #") "C17709") (field (name "Comment") "0805W8F4703T5E"))
      (libsource (lib "JLC_PCB") (part "0805W8F4703T5E"))
    )
    (comp (ref "R26")
      (value "470k")
      (footprint "R_0805")
      (description "R - RESISTOR - SMD - 470k - 1% - 0805")
      (fields (field (name "LCSC PART #") "C17709") (field (name "Comment") "0805W8F4703T5E"))
      (libsource (lib "JLC_PCB") (part "0805W8F4703T5E"))
    )
    (comp (ref "R27")
      (value "1k")
      (footprint "R_0402")
      (description "R - RESISTOR - SMD - 1k - 1% - 0402")
      (fields (field (name "LCSC PART #") "C11702") (field (name "Comment") "0402WGF1001TCE"))
      (libsource (lib "JLC_PCB") (part "0402WGF1001TCE"))
    )
    (comp (ref "R29")
      (value "1k")
      (footprint "R_0402")
      (description "R - RESISTOR - SMD - 1k - 1% - 0402")
      (fields (field (name "LCSC PART #") "C11702") (field (name "Comment") "0402WGF1001TCE"))
      (libsource (lib "JLC_PCB") (part "0402WGF1001TCE"))
    )
    (comp (ref "R30")
      (value "2.2k")
      (footprint "R_0402")
      (description "R - RESISTOR - SMD - 2.2k - 1% - 0402")
      (fields (field (name "LCSC PART #") "C25879") (field (name "Comment") "0402WGF2201TCE"))
      (libsource (lib "JLC_PCB") (part "0402WGF2201TCE"))
    )
    (comp (ref "R31")
      (value "10R")
      (footprint "R_0603")
      (description "R - RESISTOR - SMD - 10R - 1% - 0603")
      (fields (field (name "LCSC PART #") "C22859") (field (name "Comment") "0603WAF100JT5E"))
      (libsource (lib "JLC_PCB") (part "0603WAF100JT5E"))
    )
    (comp (ref "R32")
      (value "10k")
      (footprint "R_0402")
      (description "R - RESISTOR - SMD - 10k - 1% - 0402")
      (fields (field (name "LCSC PART #") "C25744") (field (name "Comment") "0402WGF1002TCE"))
      (libsource (lib "JLC_PCB") (part "0402WGF1002TCE"))
    )
    (comp (ref "R33")
      (value "4.7k")
      (footprint "R_0402")
      (description "R - RESISTOR - SMD - 4.7k - 1% - 0402")
      (fields (field (name "LCSC PART #") "C25900") (field (name "Comment") "0402WGF4701TCE"))
      (libsource (lib "JLC_PCB") (part "0402WGF4701TCE"))
    )
    (comp (ref "R34")
      (value "1R")
      (footprint "R_0603")
      (description "R - RESISTOR - SMD - 1R - 1% -  0603")
      (fields (field (name "LCSC PART #") "C22936") (field (name "Comment") "0603WAF100KT5E"))
      (libsource (lib "JLC_PCB") (part "0603WAF100KT5E"))
    )
    (comp (ref "R35")
      (value "4.7k")
      (footprint "R_0402")
      (description "R - RESISTOR - SMD - 4.7k - 1% - 0402")
      (fields (field (name "LCSC PART #") "C25900") (field (name "Comment") "0402WGF4701TCE"))
      (libsource (lib "JLC_PCB") (part "0402WGF4701TCE"))
    )
    (comp (ref "R36")
      (value "10R")
      (footprint "R_0603")
      (description "R - RESISTOR - SMD - 10R - 1% - 0603")
      (fields (field (name "LCSC PART #") "C22859") (field (name "Comment") "0603WAF100JT5E"))
      (libsource (lib "JLC_PCB") (part "0603WAF100JT5E"))
    )
    (comp (ref "R37")
      (value "10k")
      (footprint "R_0402")
      (description "R - RESISTOR - SMD - 10k - 1% - 0402")
      (fields (field (name "LCSC PART #") "C25744") (field (name "Comment") "0402WGF1002TCE"))
      (libsource (lib "JLC_PCB") (part "0402WGF1002TCE"))
    )
    (comp (ref "R38")
      (value "47R")
      (footprint "R_0402")
      (description "R - RESISTOR - SMD - 47R - 1% - 0402")
      (fields (field (name "LCSC PART #") "C25118") (field (name "Comment") "0402WGF470JTCE"))
      (libsource (lib "JLC_PCB") (part "0402WGF470JTCE"))
    )
    (comp (ref "R39")
      (value "47R")
      (footprint "R_0402")
      (description "R - RESISTOR - SMD - 47R - 1% - 0402")
      (fields (field (name "LCSC PART #") "C25118") (field (name "Comment") "0402WGF470JTCE"))
      (libsource (lib "JLC_PCB") (part "0402WGF470JTCE"))
    )
    (comp (ref "R40")
      (value "47R")
      (footprint "R_0402")
      (description "R - RESISTOR - SMD - 47R - 1% - 0402")
      (fields (field (name "LCSC PART #") "C25118") (field (name "Comment") "0402WGF470JTCE"))
      (libsource (lib "JLC_PCB") (part "0402WGF470JTCE"))
    )
    (comp (ref "R41")
      (value "4.7k")
      (footprint "R_0402")
      (description "R - RESISTOR - SMD - 4.7k - 1% - 0402")
      (fields (field (name "LCSC PART #") "C25900") (field (name "Comment") "0402WGF4701TCE"))
      (libsource (lib "JLC_PCB") (part "0402WGF4701TCE"))
    )
    (comp (ref "R42")
      (value "10R")
      (footprint "R_0603")
      (description "R - RESISTOR - SMD - 10R - 1% - 0603")
      (fields (field (name "LCSC PART #") "C22859") (field (name "Comment") "0603WAF100JT5E"))
      (libsource (lib "JLC_PCB") (part "0603WAF100JT5E"))
    )
    (comp (ref "R43")
      (value "10k")
      (footprint "R_0402")
      (description "R - RESISTOR - SMD - 10k - 1% - 0402")
      (fields (field (name "LCSC PART #") "C25744") (field (name "Comment") "0402WGF1002TCE"))
      (libsource (lib "JLC_PCB") (part "0402WGF1002TCE"))
    )
    (comp (ref "R44")
      (value "4.7k")
      (footprint "R_0402")
      (description "R - RESISTOR - SMD - 4.7k - 1% - 0402")
      (fields (field (name "LCSC PART #") "C25900") (field (name "Comment") "0402WGF4701TCE"))
      (libsource (lib "JLC_PCB") (part "0402WGF4701TCE"))
    )
    (comp (ref "R90")
      (value "10k")
      (footprint "R_0402")
      (description "R - RESISTOR - SMD - 10k - 1% - 0402")
      (fields (field (name "LCSC PART #") "C25744") (field (name "Comment") "0402WGF1002TCE"))
      (libsource (lib "JLC_PCB") (part "0402WGF1002TCE"))
    )
    (comp (ref "R91")
      (value "10k")
      (footprint "R_0402")
      (description "R - RESISTOR - SMD - 10k - 1% - 0402")
      (fields (field (name "LCSC PART #") "C25744") (field (name "Comment") "0402WGF1002TCE"))
      (libsource (lib "JLC_PCB") (part "0402WGF1002TCE"))
    )
    (comp (ref "R92")
      (value "10k")
      (footprint "R_0402")
      (description "R - RESISTOR - SMD - 10k - 1% - 0402")
      (fields (field (name "LCSC PART #") "C25744") (field (name "Comment") "0402WGF1002TCE"))
      (libsource (lib "JLC_PCB") (part "0402WGF1002TCE"))
    )
    (comp (ref "R94")
      (value "10k")
      (footprint "R_0402")
      (description "R - RESISTOR - SMD - 10k - 1% - 0402")
      (fields (field (name "LCSC PART #") "C25744") (field (name "Comment") "0402WGF1002TCE"))
      (libsource (lib "JLC_PCB") (part "0402WGF1002TCE"))
    )
    (comp (ref "RF")
      (value "1R")
      (footprint "R_1206")
      (description "R - RESISTOR - SMD - 1R - 1% - 1206")
      (fields (field (name "LCSC PART #") "C17928") (field (name "Comment") "1206W4F1000T5E"))
      (libsource (lib "JLC_PCB") (part "1206W4F1000T5E"))
    )
    (comp (ref "RF_B")
      (value "1R")
      (footprint "R_1206")
      (description "R - RESISTOR - SMD - 1R - 1% - 1206")
      (fields (field (name "LCSC PART #") "C17928") (field (name "Comment") "1206W4F1000T5E"))
      (libsource (lib "JLC_PCB") (part "1206W4F1000T5E"))
    )
    (comp (ref "RF_C")
      (value "1R")
      (footprint "R_1206")
      (description "R - RESISTOR - SMD - 1R - 1% - 1206")
      (fields (field (name "LCSC PART #") "C17928") (field (name "Comment") "1206W4F1000T5E"))
      (libsource (lib "JLC_PCB") (part "1206W4F1000T5E"))
    )
    (comp (ref "RF_D")
      (value "1R")
      (footprint "R_1206")
      (description "R - RESISTOR - SMD - 1R - 1% - 1206")
      (fields (field (name "LCSC PART #") "C17928") (field (name "Comment") "1206W4F1000T5E"))
      (libsource (lib "JLC_PCB") (part "1206W4F1000T5E"))
    )
    (comp (ref "RF_E")
      (value "1R")
      (footprint "R_1206")
      (description "R - RESISTOR - SMD - 1R - 1% - 1206")
      (fields (field (name "LCSC PART #") "C17928") (field (name "Comment") "1206W4F1000T5E"))
      (libsource (lib "JLC_PCB") (part "1206W4F1000T5E"))
    )
    (comp (ref "RF_F")
      (value "1R")
      (footprint "R_1206")
      (description "R - RESISTOR - SMD - 1R - 1% - 1206")
      (fields (field (name "LCSC PART #") "C17928") (field (name "Comment") "1206W4F1000T5E"))
      (libsource (lib "JLC_PCB") (part "1206W4F1000T5E"))
    )
    (comp (ref "RF_G")
      (value "1R")
      (footprint "R_1206")
      (description "R - RESISTOR - SMD - 1R - 1% - 1206")
      (fields (field (name "LCSC PART #") "C17928") (field (name "Comment") "1206W4F1000T5E"))
      (libsource (lib "JLC_PCB") (part "1206W4F1000T5E"))
    )
    (comp (ref "U1")
      (value "STM32L475RCT3")
      (footprint "QFP-64-P0.5MM")
      (description "U - IC - MCU 32BIT LOW POWER 64LQFP")
      (fields (field (name "ALTIUM_VALUE") "STM32L475RCT3") (field (name "LCSC PART #") "C1235405"))
      (libsource (lib "JLC_PCB") (part "STM32L475RCT3"))
    )
    (comp (ref "U2")
      (value "UCC21520A")
      (footprint "FOOTPRINTS:SOIC-16-P1.27-W7.5")
      (description "U - IC - GATE DRIVER, Half Bridge, Isolated")
      (fields (field (name "LCSC PART #") "C601651"))
      (libsource (lib "JLC_PCB") (part "UCC21520A"))
    )
    (comp (ref "U4")
      (value "HT7533-1")
      (footprint "SOT-223-3")
      (description "U - IC - 3V3 Power Regulator")
      (fields (field (name "LCSC PART #") "C14289"))
      (libsource (lib "JLC_PCB") (part "HT7533-1"))
    )
    (comp (ref "U5")
      (value "UCC21520A")
      (footprint "FOOTPRINTS:SOIC-16-P1.27-W7.5")
      (description "U - IC - GATE DRIVER, Half Bridge, Isolated")
      (fields (field (name "LCSC PART #") "C601651"))
      (libsource (lib "JLC_PCB") (part "UCC21520A"))
    )
    (comp (ref "Y1")
      (value "X322512MSB4SI")
      (footprint "X322512MSB4SI")
      (description "Y - RESONATOR - 12MHZ ±10PPM")
      (fields (field (name "ALTIUM_VALUE") "12MHz") (field (name "LCSC PART #") "C9002"))
      (libsource (lib "JLC_PCB") (part "X322512MSB4SI"))
    )
  )
  (nets
    (net (code "1") (name "/+3V3") (class "Default")
      (node (ref "C1") (pin "1") (pinfunction "1_1") (pintype "passive"))
      (node (ref "C14") (pin "2") (pinfunction "2_2") (pintype "passive"))
      (node (ref "C18") (pin "2") (pinfunction "2_2") (pintype "passive"))
      (node (ref "C2") (pin "1") (pinfunction "1_1") (pintype "passive"))
      (node (ref "C3") (pin "1") (pinfunction "1_1") (pintype "passive"))
      (node (ref "C38") (pin "1") (pinfunction "1_1") (pintype "passive"))
      (node (ref "C39") (pin "1") (pinfunction "1_1") (pintype "passive"))
      (node (ref "C4") (pin "1") (pinfunction "1_1") (pintype "passive"))
      (node (ref "C45") (pin "1") (pinfunction "1_1") (pintype "passive"))
      (node (ref "C59") (pin "1") (pinfunction "1_1") (pintype "passive"))
      (node (ref "C64") (pin "1") (pinfunction "1_1") (pintype "passive"))
      (node (ref "C65") (pin "1") (pinfunction "1_1") (pintype "passive"))
      (node (ref "C69") (pin "1") (pinfunction "1_1") (pintype "passive"))
      (node (ref "C70") (pin "1") (pinfunction "1_1") (pintype "passive"))
      (node (ref "C75") (pin "1") (pinfunction "1_1") (pintype "passive"))
      (node (ref "IC4") (pin "8") (pinfunction "DVDD_8") (pintype "passive"))
      (node (ref "IC5") (pin "8") (pinfunction "DVDD_8") (pintype "passive"))
      (node (ref "IC9") (pin "8") (pinfunction "DVDD_8") (pintype "passive"))
      (node (ref "R94") (pin "1") (pinfunction "1_1") (pintype "passive"))
      (node (ref "U1") (pin "1") (pinfunction "VBAT_1") (pintype "passive"))
      (node (ref "U1") (pin "13") (pinfunction "VDDA_13") (pintype "passive"))
      (node (ref "U1") (pin "19") (pinfunction "VDD_19") (pintype "passive"))
      (node (ref "U1") (pin "32") (pinfunction "VDD_32") (pintype "passive"))
      (node (ref "U1") (pin "48") (pinfunction "VDDUSB_48") (pintype "passive"))
      (node (ref "U1") (pin "64") (pinfunction "VDD_64") (pintype "passive"))
      (node (ref "U2") (pin "3") (pinfunction "VCCI_3") (pintype "passive"))
      (node (ref "U4") (pin "3") (pinfunction "Vout_3") (pintype "output"))
      (node (ref "U5") (pin "3") (pinfunction "VCCI_3") (pintype "passive"))
    )
    (net (code "2") (name "/+5V_1") (class "Default")
      (node (ref "C41") (pin "1") (pinfunction "1_1") (pintype "passive"))
      (node (ref "C42") (pin "1") (pinfunction "1_1") (pintype "passive"))
      (node (ref "C47") (pin "1") (pinfunction "1_1") (pintype "passive"))
      (node (ref "C48") (pin "1") (pinfunction "1_1") (pintype "passive"))
      (node (ref "C54") (pin "1") (pinfunction "1_1") (pintype "passive"))
      (node (ref "IC4") (pin "1") (pinfunction "AVDD_1") (pintype "passive"))
      (node (ref "IC5") (pin "1") (pinfunction "AVDD_1") (pintype "passive"))
      (node (ref "PS2") (pin "1") (pinfunction "Vout_1") (pintype "output"))
    )
    (net (code "3") (name "/+5V_D") (class "Default")
      (node (ref "C37") (pin "1") (pinfunction "1_1") (pintype "passive"))
      (node (ref "C67") (pin "1") (pinfunction "1_1") (pintype "passive"))
      (node (ref "C68") (pin "1") (pinfunction "1_1") (pintype "passive"))
      (node (ref "IC9") (pin "1") (pinfunction "AVDD_1") (pintype "passive"))
      (node (ref "PS1") (pin "1") (pinfunction "Vout_1") (pintype "output"))
    )
    (net (code "4") (name "/+12V") (class "Default")
      (node (ref "C25") (pin "2") (pinfunction "2_2") (pintype "passive"))
      (node (ref "C34") (pin "1") (pinfunction "1_1") (pintype "passive"))
      (node (ref "C44") (pin "1") (pinfunction "1_1") (pintype "passive"))
      (node (ref "C8") (pin "2") (pinfunction "2_2") (pintype "passive"))
      (node (ref "D8") (pin "2") (pinfunction "A_2") (pintype "passive"))
      (node (ref "D9") (pin "2") (pinfunction "A_2") (pintype "passive"))
      (node (ref "GTI_PS_A") (pin "5") (pinfunction "+VO_5") (pintype "output"))
      (node (ref "PS1") (pin "3") (pinfunction "VIN_3") (pintype "input"))
      (node (ref "R90") (pin "1") (pinfunction "1_1") (pintype "passive"))
      (node (ref "U2") (pin "11") (pinfunction "VDDB_11") (pintype "passive"))
      (node (ref "U5") (pin "11") (pinfunction "VDDB_11") (pintype "passive"))
    )
    (net (code "5") (name "/CLK_SigmaDelta") (class "Default")
      (node (ref "IC4") (pin "7") (pinfunction "CLKIN_7") (pintype "passive"))
      (node (ref "IC5") (pin "7") (pinfunction "CLKIN_7") (pintype "passive"))
      (node (ref "IC9") (pin "7") (pinfunction "CLKIN_7") (pintype "passive"))
      (node (ref "U1") (pin "10") (pinfunction "PC2_10") (pintype "passive"))
    )
    (net (code "6") (name "/D1_Sigma_Delta") (class "Default")
      (node (ref "IC4") (pin "6") (pinfunction "DOUT_6") (pintype "passive"))
      (node (ref "U1") (pin "35") (pinfunction "PB14_35") (pintype "passive"))
    )
    (net (code "7") (name "/D2_Sigma_Delta") (class "Default")
      (node (ref "IC5") (pin "6") (pinfunction "DOUT_6") (pintype "passive"))
      (node (ref "U1") (pin "33") (pinfunction "PB12_33") (pintype "passive"))
    )
    (net (code "8") (name "/D4_Sigma_Delta") (class "Default")
      (node (ref "IC9") (pin "6") (pinfunction "DOUT_6") (pintype "passive"))
      (node (ref "U1") (pin "27") (pinfunction "PB1_27") (pintype "passive"))
    )
    (net (code "9") (name "/GNDD") (class "Default")
      (node (ref "C1") (pin "2") (pinfunction "2_2") (pintype "passive"))
      (node (ref "C10") (pin "2") (pinfunction "2_2") (pintype "passive"))
      (node (ref "C11") (pin "1") (pinfunction "1_1") (pintype "passive"))
      (node (ref "C12") (pin "2") (pinfunction "2_2") (pintype "passive"))
      (node (ref "C13") (pin "2") (pinfunction "2_2") (pintype "passive"))
      (node (ref "C14") (pin "1") (pinfunction "1_1") (pintype "passive"))
      (node (ref "C15") (pin "2") (pinfunction "2_2") (pintype "passive"))
      (node (ref "C16") (pin "2") (pinfunction "2_2") (pintype "passive"))
      (node (ref "C17") (pin "2") (pinfunction "2_2") (pintype "passive"))
      (node (ref "C18") (pin "1") (pinfunction "1_1") (pintype "passive"))
      (node (ref "C2") (pin "2") (pinfunction "2_2") (pintype "passive"))
      (node (ref "C26") (pin "2") (pinfunction "2_2") (pintype "passive"))
      (node (ref "C29") (pin "2") (pinfunction "2_2") (pintype "passive"))
      (node (ref "C3") (pin "2") (pinfunction "2_2") (pintype "passive"))
      (node (ref "C30") (pin "2") (pinfunction "2_2") (pintype "passive"))
      (node (ref "C31") (pin "1") (pinfunction "1_1") (pintype "passive"))
      (node (ref "C38") (pin "2") (pinfunction "2_2") (pintype "passive"))
      (node (ref "C39") (pin "2") (pinfunction "2_2") (pintype "passive"))
      (node (ref "C4") (pin "2") (pinfunction "2_2") (pintype "passive"))
      (node (ref "C43") (pin "2") (pinfunction "2_2") (pintype "passive"))
      (node (ref "C45") (pin "2") (pinfunction "2_2") (pintype "passive"))
      (node (ref "C59") (pin "2") (pinfunction "2_2") (pintype "passive"))
      (node (ref "C62") (pin "2") (pinfunction "2_2") (pintype "passive"))
      (node (ref "C64") (pin "2") (pinfunction "2_2") (pintype "passive"))
      (node (ref "C65") (pin "2") (pinfunction "2_2") (pintype "passive"))
      (node (ref "C69") (pin "2") (pinfunction "2_2") (pintype "passive"))
      (node (ref "C70") (pin "2") (pinfunction "2_2") (pintype "passive"))
      (node (ref "C72") (pin "2") (pinfunction "2_2") (pintype "passive"))
      (node (ref "C74") (pin "2") (pinfunction "2_2") (pintype "passive"))
      (node (ref "C75") (pin "2") (pinfunction "2_2") (pintype "passive"))
      (node (ref "D4") (pin "1") (pinfunction "K_1") (pintype "passive"))
      (node (ref "D92") (pin "1") (pinfunction "K_1") (pintype "passive"))
      (node (ref "D94") (pin "1") (pinfunction "K_1") (pintype "passive"))
      (node (ref "GTI_PS_A") (pin "1") (pinfunction "GND_1") (pintype "power_in"))
      (node (ref "GTI_PS_B") (pin "1") (pinfunction "GND_1") (pintype "power_in"))
      (node (ref "GTI_T_A") (pin "3") (pinfunction "-Vo_3") (pintype "passive"))
      (node (ref "GT_J_SWD") (pin "3") (pinfunction "3_3") (pintype "passive"))
      (node (ref "GT_J_SWD") (pin "4") (pinfunction "4_4") (pintype "passive"))
      (node (ref "IC4") (pin "5") (pinfunction "DGND_5") (pintype "passive"))
      (node (ref "IC5") (pin "5") (pinfunction "DGND_5") (pintype "passive"))
      (node (ref "IC9") (pin "5") (pinfunction "DGND_5") (pintype "passive"))
      (node (ref "R33") (pin "1") (pinfunction "1_1") (pintype "passive"))
      (node (ref "R44") (pin "1") (pinfunction "1_1") (pintype "passive"))
      (node (ref "U1") (pin "12") (pinfunction "VSSA_12") (pintype "passive"))
      (node (ref "U1") (pin "18") (pinfunction "VSS_18") (pintype "passive"))
      (node (ref "U1") (pin "31") (pinfunction "VSS_31") (pintype "passive"))
      (node (ref "U1") (pin "47") (pinfunction "VSS_47") (pintype "passive"))
      (node (ref "U1") (pin "60") (pinfunction "BOOT0_60") (pintype "passive"))
      (node (ref "U1") (pin "63") (pinfunction "VSS_63") (pintype "passive"))
      (node (ref "U2") (pin "4") (pinfunction "GND_4") (pintype "passive"))
      (node (ref "U4") (pin "1") (pinfunction "GND_1") (pintype "power_in"))
      (node (ref "U5") (pin "4") (pinfunction "GND_4") (pintype "passive"))
    )
    (net (code "10") (name "/HV_LIVE") (class "Default")
      (node (ref "C22") (pin "2") (pinfunction "2_2") (pintype "passive"))
      (node (ref "GTI_D_TVS_A") (pin "1") (pinfunction "K_1") (pintype "passive"))
      (node (ref "GT_J_A") (pin "1") (pinfunction "1_1") (pintype "passive"))
      (node (ref "GT_L5") (pin "4") (pinfunction "4_4") (pintype "passive"))
    )
    (net (code "11") (name "/HV_NEU") (class "Default")
      (node (ref "C28") (pin "1") (pinfunction "1_1") (pintype "passive"))
      (node (ref "GTI_D_TVS_A") (pin "2") (pinfunction "A_2") (pintype "passive"))
      (node (ref "GT_J_B") (pin "1") (pinfunction "1_1") (pintype "passive"))
      (node (ref "GT_L5") (pin "3") (pinfunction "3_3") (pintype "passive"))
    )
    (net (code "12") (name "/Line_GND") (class "Default")
      (node (ref "C27_B") (pin "1") (pinfunction "1_1") (pintype "passive"))
      (node (ref "C41") (pin "2") (pinfunction "2_2") (pintype "passive"))
      (node (ref "C42") (pin "2") (pinfunction "2_2") (pintype "passive"))
      (node (ref "C47") (pin "2") (pinfunction "2_2") (pintype "passive"))
      (node (ref "C48") (pin "2") (pinfunction "2_2") (pintype "passive"))
      (node (ref "C49") (pin "2") (pinfunction "2_2") (pintype "passive"))
      (node (ref "C51") (pin "2") (pinfunction "2_2") (pintype "passive"))
      (node (ref "C54") (pin "2") (pinfunction "2_2") (pintype "passive"))
      (node (ref "D91") (pin "1") (pinfunction "K_1") (pintype "passive"))
      (node (ref "GTI_D_TVS_B") (pin "2") (pinfunction "A_2") (pintype "passive"))
      (node (ref "GTI_PS_B") (pin "4") (pinfunction "0V_4") (pintype "passive"))
      (node (ref "GTI_T_A") (pin "2") (pinfunction "AC_2") (pintype "passive"))
      (node (ref "GT_L5") (pin "2") (pinfunction "2_2") (pintype "passive"))
      (node (ref "IC4") (pin "4") (pinfunction "AGND_4") (pintype "passive"))
      (node (ref "IC5") (pin "4") (pinfunction "AGND_4") (pintype "passive"))
      (node (ref "PS2") (pin "2") (pinfunction "GND_2") (pintype "power_in"))
      (node (ref "R12") (pin "2") (pinfunction "2_2") (pintype "passive"))
      (node (ref "R14") (pin "1") (pinfunction "1_1") (pintype "passive"))
      (node (ref "R19") (pin "2") (pinfunction "2_2") (pintype "passive"))
      (node (ref "R20") (pin "2") (pinfunction "2_2") (pintype "passive"))
    )
    (net (code "13") (name "/Line_Isense") (class "Default")
      (node (ref "GT_L_VC_A") (pin "1") (pinfunction "1_1") (pintype "passive"))
      (node (ref "R14") (pin "2") (pinfunction "2_2") (pintype "passive"))
      (node (ref "R18") (pin "2") (pinfunction "2_2") (pintype "passive"))
    )
    (net (code "14") (name "/Line_Vsense") (class "Default")
      (node (ref "C40") (pin "1") (pinfunction "1_1") (pintype "passive"))
      (node (ref "IC4") (pin "2") (pinfunction "INP_2") (pintype "passive"))
      (node (ref "R12") (pin "1") (pinfunction "1_1") (pintype "passive"))
      (node (ref "R9") (pin "1") (pinfunction "1_1") (pintype "passive"))
    )
    (net (code "15") (name "/NRST") (class "Default")
      (node (ref "C10") (pin "1") (pinfunction "1_1") (pintype "passive"))
      (node (ref "U1") (pin "7") (pinfunction "NRST_7") (pintype "passive"))
    )
    (net (code "16") (name "/Out_B") (class "Default")
      (node (ref "C20") (pin "1") (pinfunction "1_1") (pintype "passive"))
      (node (ref "GT_L_VB_G") (pin "1") (pinfunction "1_1") (pintype "passive"))
      (node (ref "GT_L_VC_A") (pin "2") (pinfunction "2_2") (pintype "passive"))
    )
    (net (code "17") (name "/PGND") (class "Default")
      (node (ref "C25") (pin "1") (pinfunction "1_1") (pintype "passive"))
      (node (ref "C33") (pin "1") (pinfunction "1_1") (pintype "passive"))
      (node (ref "C34") (pin "2") (pinfunction "2_2") (pintype "passive"))
      (node (ref "C37") (pin "2") (pinfunction "2_2") (pintype "passive"))
      (node (ref "C44") (pin "2") (pinfunction "2_2") (pintype "passive"))
      (node (ref "C5") (pin "2") (pinfunction "2_2") (pintype "passive"))
      (node (ref "C67") (pin "2") (pinfunction "2_2") (pintype "passive"))
      (node (ref "C68") (pin "2") (pinfunction "2_2") (pintype "passive"))
      (node (ref "C8") (pin "1") (pinfunction "1_1") (pintype "passive"))
      (node (ref "D90") (pin "1") (pinfunction "K_1") (pintype "passive"))
      (node (ref "GTI_C_BULK_A") (pin "1") (pinfunction "1_1") (pintype "passive"))
      (node (ref "GTI_C_BULK_B") (pin "1") (pinfunction "1_1") (pintype "passive"))
      (node (ref "GTI_C_BULK_C") (pin "1") (pinfunction "1_1") (pintype "passive"))
      (node (ref "GTI_C_BULK_D") (pin "1") (pinfunction "1_1") (pintype "passive"))
      (node (ref "GTI_C_BULK_E") (pin "1") (pinfunction "1_1") (pintype "passive"))
      (node (ref "GTI_D_TVS_C") (pin "2") (pinfunction "A_2") (pintype "passive"))
      (node (ref "GTI_D_TVS_D") (pin "2") (pinfunction "A_2") (pintype "passive"))
      (node (ref "GTI_PS_A") (pin "4") (pinfunction "0V_4") (pintype "passive"))
      (node (ref "GT_J_D") (pin "1") (pinfunction "1_1") (pintype "passive"))
      (node (ref "GT_J_G") (pin "1") (pinfunction "1_1") (pintype "passive"))
      (node (ref "IC9") (pin "4") (pinfunction "AGND_4") (pintype "passive"))
      (node (ref "PS1") (pin "2") (pinfunction "GND_2") (pintype "power_in"))
      (node (ref "Q3") (pin "1_3") (pinfunction "S_1_3") (pintype "passive"))
      (node (ref "Q5") (pin "1_3") (pinfunction "S_1_3") (pintype "passive"))
      (node (ref "R27") (pin "2") (pinfunction "2_2") (pintype "passive"))
      (node (ref "R29") (pin "2") (pinfunction "2_2") (pintype "passive"))
      (node (ref "R32") (pin "1") (pinfunction "1_1") (pintype "passive"))
      (node (ref "R43") (pin "1") (pinfunction "1_1") (pintype "passive"))
      (node (ref "U2") (pin "9") (pinfunction "VSSB_9") (pintype "passive"))
      (node (ref "U5") (pin "9") (pinfunction "VSSB_9") (pintype "passive"))
    )
    (net (code "18") (name "/PWM_A_H") (class "Default")
      (node (ref "R2") (pin "1") (pinfunction "1_1") (pintype "passive"))
      (node (ref "U1") (pin "41") (pinfunction "PA8_41") (pintype "passive"))
    )
    (net (code "19") (name "/PWM_A_L") (class "Default")
      (node (ref "R3") (pin "1") (pinfunction "1_1") (pintype "passive"))
      (node (ref "U1") (pin "23") (pinfunction "PA7_23") (pintype "passive"))
    )
    (net (code "20") (name "/PWM_B_H") (class "Default")
      (node (ref "R38") (pin "1") (pinfunction "1_1") (pintype "passive"))
      (node (ref "U1") (pin "42") (pinfunction "PA9_42") (pintype "passive"))
    )
    (net (code "21") (name "/PWM_B_L") (class "Default")
      (node (ref "R39") (pin "1") (pinfunction "1_1") (pintype "passive"))
      (node (ref "U1") (pin "26") (pinfunction "PB0_26") (pintype "passive"))
    )
    (net (code "22") (name "/PWM_Disable") (class "Default")
      (node (ref "R40") (pin "1") (pinfunction "1_1") (pintype "passive"))
      (node (ref "U1") (pin "16") (pinfunction "PA2_16") (pintype "passive"))
    )
    (net (code "23") (name "/Relay_Ctrl") (class "Default")
      (node (ref "U1") (pin "44") (pinfunction "PA11_44") (pintype "passive"))
    )
    (net (code "25") (name "/SWDCK") (class "Default")
      (node (ref "GT_J_SWD") (pin "6") (pinfunction "6_6") (pintype "passive"))
      (node (ref "U1") (pin "49") (pinfunction "PA14_49") (pintype "passive"))
    )
    (net (code "26") (name "/SWDIO") (class "Default")
      (node (ref "GT_J_SWD") (pin "2") (pinfunction "2_2") (pintype "passive"))
      (node (ref "U1") (pin "46") (pinfunction "PA13_46") (pintype "passive"))
    )
    (net (code "27") (name "/VBUS") (class "Default")
      (node (ref "C33") (pin "2") (pinfunction "2_2") (pintype "passive"))
      (node (ref "C5") (pin "1") (pinfunction "1_1") (pintype "passive"))
      (node (ref "GTI_C_BULK_A") (pin "2") (pinfunction "2_2") (pintype "passive"))
      (node (ref "GTI_C_BULK_B") (pin "2") (pinfunction "2_2") (pintype "passive"))
      (node (ref "GTI_C_BULK_C") (pin "2") (pinfunction "2_2") (pintype "passive"))
      (node (ref "GTI_C_BULK_D") (pin "2") (pinfunction "2_2") (pintype "passive"))
      (node (ref "GTI_C_BULK_E") (pin "2") (pinfunction "2_2") (pintype "passive"))
      (node (ref "GTI_D_TVS_C") (pin "1") (pinfunction "K_1") (pintype "passive"))
      (node (ref "GTI_D_TVS_D") (pin "1") (pinfunction "K_1") (pintype "passive"))
      (node (ref "GTI_T_A") (pin "1") (pinfunction "AC_1") (pintype "passive"))
      (node (ref "GT_J_E") (pin "1") (pinfunction "1_1") (pintype "passive"))
      (node (ref "GT_J_F") (pin "1") (pinfunction "1_1") (pintype "passive"))
      (node (ref "Q1") (pin "5_8") (pinfunction "D_5_8") (pintype "passive"))
      (node (ref "Q4") (pin "5_8") (pinfunction "D_5_8") (pintype "passive"))
      (node (ref "R26") (pin "2") (pinfunction "2_2") (pintype "passive"))
    )
    (net (code "28") (name "/VCC") (class "Default")
      (node (ref "C43") (pin "1") (pinfunction "1_1") (pintype "passive"))
      (node (ref "C62") (pin "1") (pinfunction "1_1") (pintype "passive"))
      (node (ref "C72") (pin "1") (pinfunction "1_1") (pintype "passive"))
      (node (ref "C74") (pin "1") (pinfunction "1_1") (pintype "passive"))
      (node (ref "GTI_PS_A") (pin "2") (pinfunction "VIN_2") (pintype "input"))
      (node (ref "GTI_PS_B") (pin "2") (pinfunction "VIN_2") (pintype "input"))
      (node (ref "GTI_T_A") (pin "4") (pinfunction "+Vo_4") (pintype "passive"))
      (node (ref "R92") (pin "1") (pinfunction "1_1") (pintype "passive"))
      (node (ref "U4") (pin "2") (pinfunction "VIN_2") (pintype "input"))
    )
    (net (code "29") (name "/VDDA_A") (class "Default")
      (node (ref "C7") (pin "2") (pinfunction "2_2") (pintype "passive"))
      (node (ref "R1") (pin "2") (pinfunction "2_2") (pintype "passive"))
      (node (ref "U2") (pin "16") (pinfunction "VDDA_16") (pintype "passive"))
    )
    (net (code "30") (name "/VDDA_B") (class "Default")
      (node (ref "C23") (pin "2") (pinfunction "2_2") (pintype "passive"))
      (node (ref "R34") (pin "1") (pinfunction "1_1") (pintype "passive"))
      (node (ref "U5") (pin "16") (pinfunction "VDDA_16") (pintype "passive"))
    )
    (net (code "31") (name "/VS_A") (class "Default")
      (node (ref "C7") (pin "1") (pinfunction "1_1") (pintype "passive"))
      (node (ref "GT_L_VA_A") (pin "2") (pinfunction "2_2") (pintype "passive"))
      (node (ref "Q1") (pin "1_3") (pinfunction "S_1_3") (pintype "passive"))
      (node (ref "Q3") (pin "5_8") (pinfunction "D_5_8") (pintype "passive"))
      (node (ref "R13") (pin "1") (pinfunction "1_1") (pintype "passive"))
      (node (ref "U2") (pin "14") (pinfunction "VSSA_14") (pintype "passive"))
    )
    (net (code "32") (name "/VS_B") (class "Default")
      (node (ref "C23") (pin "1") (pinfunction "1_1") (pintype "passive"))
      (node (ref "GT_L_VB_A") (pin "2") (pinfunction "2_2") (pintype "passive"))
      (node (ref "Q4") (pin "1_3") (pinfunction "S_1_3") (pintype "passive"))
      (node (ref "Q5") (pin "5_8") (pinfunction "D_5_8") (pintype "passive"))
      (node (ref "R37") (pin "1") (pinfunction "1_1") (pintype "passive"))
      (node (ref "U5") (pin "14") (pinfunction "VSSA_14") (pintype "passive"))
    )
    (net (code "33") (name "/V_HOT") (class "Default")
      (node (ref "C27_B") (pin "2") (pinfunction "2_2") (pintype "passive"))
      (node (ref "GTI_D_TVS_B") (pin "1") (pinfunction "K_1") (pintype "passive"))
      (node (ref "GT_L5") (pin "1") (pinfunction "1_1") (pintype "passive"))
      (node (ref "GT_L_VA_G") (pin "1") (pinfunction "1_1") (pintype "passive"))
      (node (ref "R5") (pin "2") (pinfunction "2_2") (pintype "passive"))
      (node (ref "RF") (pin "2") (pinfunction "2_2") (pintype "passive"))
    )
    (net (code "34") (name "Net-(C20-Pad2)") (class "Default")
      (node (ref "C20") (pin "2") (pinfunction "2_2") (pintype "passive"))
      (node (ref "RF_G") (pin "1") (pinfunction "1_1") (pintype "passive"))
    )
    (net (code "35") (name "Net-(C22-Pad1)") (class "Default")
      (node (ref "C22") (pin "1") (pinfunction "1_1") (pintype "passive"))
      (node (ref "C28") (pin "2") (pinfunction "2_2") (pintype "passive"))
      (node (ref "GT_J_C") (pin "1") (pinfunction "1_1") (pintype "passive"))
    )
    (net (code "36") (name "Net-(D4-A)") (class "Default")
      (node (ref "D4") (pin "2") (pinfunction "A_2") (pintype "passive"))
      (node (ref "R30") (pin "2") (pinfunction "2_2") (pintype "passive"))
    )
    (net (code "37") (name "Net-(D5-A)") (class "Default")
      (node (ref "D5") (pin "2") (pinfunction "A_2") (pintype "passive"))
      (node (ref "Q1") (pin "4") (pinfunction "G_4") (pintype "passive"))
      (node (ref "R11") (pin "1") (pinfunction "1_1") (pintype "passive"))
      (node (ref "R13") (pin "2") (pinfunction "2_2") (pintype "passive"))
    )
    (net (code "38") (name "Net-(D5-K)") (class "Default")
      (node (ref "D5") (pin "1") (pinfunction "K_1") (pintype "passive"))
      (node (ref "R6") (pin "2") (pinfunction "2_2") (pintype "passive"))
    )
    (net (code "39") (name "Net-(D7-A)") (class "Default")
      (node (ref "D7") (pin "2") (pinfunction "A_2") (pintype "passive"))
      (node (ref "Q3") (pin "4") (pinfunction "G_4") (pintype "passive"))
      (node (ref "R31") (pin "1") (pinfunction "1_1") (pintype "passive"))
      (node (ref "R32") (pin "2") (pinfunction "2_2") (pintype "passive"))
    )
    (net (code "40") (name "Net-(D7-K)") (class "Default")
      (node (ref "D7") (pin "1") (pinfunction "K_1") (pintype "passive"))
      (node (ref "R15") (pin "2") (pinfunction "2_2") (pintype "passive"))
    )
    (net (code "41") (name "Net-(D8-K)") (class "Default")
      (node (ref "D8") (pin "1") (pinfunction "K_1") (pintype "passive"))
      (node (ref "R1") (pin "1") (pinfunction "1_1") (pintype "passive"))
    )
    (net (code "42") (name "Net-(D9-K)") (class "Default")
      (node (ref "D9") (pin "1") (pinfunction "K_1") (pintype "passive"))
      (node (ref "R34") (pin "2") (pinfunction "2_2") (pintype "passive"))
    )
    (net (code "43") (name "Net-(D10-A)") (class "Default")
      (node (ref "D10") (pin "2") (pinfunction "A_2") (pintype "passive"))
      (node (ref "Q4") (pin "4") (pinfunction "G_4") (pintype "passive"))
      (node (ref "R36") (pin "1") (pinfunction "1_1") (pintype "passive"))
      (node (ref "R37") (pin "2") (pinfunction "2_2") (pintype "passive"))
    )
    (net (code "44") (name "Net-(D10-K)") (class "Default")
      (node (ref "D10") (pin "1") (pinfunction "K_1") (pintype "passive"))
      (node (ref "R35") (pin "2") (pinfunction "2_2") (pintype "passive"))
    )
    (net (code "45") (name "Net-(D11-A)") (class "Default")
      (node (ref "D11") (pin "2") (pinfunction "A_2") (pintype "passive"))
      (node (ref "Q5") (pin "4") (pinfunction "G_4") (pintype "passive"))
      (node (ref "R42") (pin "1") (pinfunction "1_1") (pintype "passive"))
      (node (ref "R43") (pin "2") (pinfunction "2_2") (pintype "passive"))
    )
    (net (code "46") (name "Net-(D11-K)") (class "Default")
      (node (ref "D11") (pin "1") (pinfunction "K_1") (pintype "passive"))
      (node (ref "R41") (pin "2") (pinfunction "2_2") (pintype "passive"))
    )
    (net (code "47") (name "Net-(D90-A)") (class "Default")
      (node (ref "D90") (pin "2") (pinfunction "A_2") (pintype "passive"))
      (node (ref "R90") (pin "2") (pinfunction "2_2") (pintype "passive"))
    )
    (net (code "48") (name "Net-(D91-A)") (class "Default")
      (node (ref "D91") (pin "2") (pinfunction "A_2") (pintype "passive"))
      (node (ref "R91") (pin "2") (pinfunction "2_2") (pintype "passive"))
    )
    (net (code "49") (name "Net-(D92-A)") (class "Default")
      (node (ref "D92") (pin "2") (pinfunction "A_2") (pintype "passive"))
      (node (ref "R92") (pin "2") (pinfunction "2_2") (pintype "passive"))
    )
    (net (code "50") (name "Net-(D94-A)") (class "Default")
      (node (ref "D94") (pin "2") (pinfunction "A_2") (pintype "passive"))
      (node (ref "R94") (pin "2") (pinfunction "2_2") (pintype "passive"))
    )
    (net (code "51") (name "Net-(GTI_PS_B-+VO)") (class "Default")
      (node (ref "C49") (pin "1") (pinfunction "1_1") (pintype "passive"))
      (node (ref "C51") (pin "1") (pinfunction "1_1") (pintype "passive"))
      (node (ref "GTI_PS_B") (pin "5") (pinfunction "+VO_5") (pintype "output"))
      (node (ref "PS2") (pin "3") (pinfunction "VIN_3") (pintype "input"))
      (node (ref "R91") (pin "1") (pinfunction "1_1") (pintype "passive"))
    )
    (net (code "52") (name "Net-(GT_L_VA_A-Pad1)") (class "Default")
      (node (ref "GT_L_VA_A") (pin "1") (pinfunction "1_1") (pintype "passive"))
      (node (ref "GT_L_VA_B") (pin "1") (pinfunction "1_1") (pintype "passive"))
    )
    (net (code "53") (name "Net-(GT_L_VA_B-Pad2)") (class "Default")
      (node (ref "GT_L_VA_B") (pin "2") (pinfunction "2_2") (pintype "passive"))
      (node (ref "GT_L_VA_G") (pin "2") (pinfunction "2_2") (pintype "passive"))
    )
    (net (code "54") (name "Net-(GT_L_VB_A-Pad1)") (class "Default")
      (node (ref "GT_L_VB_A") (pin "1") (pinfunction "1_1") (pintype "passive"))
      (node (ref "GT_L_VB_B") (pin "1") (pinfunction "1_1") (pintype "passive"))
    )
    (net (code "55") (name "Net-(GT_L_VB_B-Pad2)") (class "Default")
      (node (ref "GT_L_VB_B") (pin "2") (pinfunction "2_2") (pintype "passive"))
      (node (ref "GT_L_VB_G") (pin "2") (pinfunction "2_2") (pintype "passive"))
    )
    (net (code "56") (name "Net-(IC4-INN)") (class "Default")
      (node (ref "C40") (pin "2") (pinfunction "2_2") (pintype "passive"))
      (node (ref "IC4") (pin "3") (pinfunction "INN_3") (pintype "passive"))
      (node (ref "R20") (pin "1") (pinfunction "1_1") (pintype "passive"))
    )
    (net (code "57") (name "Net-(IC5-INN)") (class "Default")
      (node (ref "C46") (pin "2") (pinfunction "2_2") (pintype "passive"))
      (node (ref "IC5") (pin "3") (pinfunction "INN_3") (pintype "passive"))
      (node (ref "R19") (pin "1") (pinfunction "1_1") (pintype "passive"))
    )
    (net (code "58") (name "Net-(IC5-INP)") (class "Default")
      (node (ref "C46") (pin "1") (pinfunction "1_1") (pintype "passive"))
      (node (ref "IC5") (pin "2") (pinfunction "INP_2") (pintype "passive"))
      (node (ref "R18") (pin "1") (pinfunction "1_1") (pintype "passive"))
    )
    (net (code "59") (name "Net-(IC9-INN)") (class "Default")
      (node (ref "C66") (pin "2") (pinfunction "2_2") (pintype "passive"))
      (node (ref "IC9") (pin "3") (pinfunction "INN_3") (pintype "passive"))
      (node (ref "R29") (pin "1") (pinfunction "1_1") (pintype "passive"))
    )
    (net (code "60") (name "Net-(IC9-INP)") (class "Default")
      (node (ref "C66") (pin "1") (pinfunction "1_1") (pintype "passive"))
      (node (ref "IC9") (pin "2") (pinfunction "INP_2") (pintype "passive"))
      (node (ref "R24") (pin "1") (pinfunction "1_1") (pintype "passive"))
      (node (ref "R27") (pin "1") (pinfunction "1_1") (pintype "passive"))
    )
    (net (code "61") (name "Net-(R5-Pad1)") (class "Default")
      (node (ref "R5") (pin "1") (pinfunction "1_1") (pintype "passive"))
      (node (ref "R8") (pin "2") (pinfunction "2_2") (pintype "passive"))
    )
    (net (code "62") (name "Net-(R8-Pad1)") (class "Default")
      (node (ref "R8") (pin "1") (pinfunction "1_1") (pintype "passive"))
      (node (ref "R9") (pin "2") (pinfunction "2_2") (pintype "passive"))
    )
    (net (code "63") (name "Net-(R24-Pad2)") (class "Default")
      (node (ref "R24") (pin "2") (pinfunction "2_2") (pintype "passive"))
      (node (ref "R25") (pin "1") (pinfunction "1_1") (pintype "passive"))
    )
    (net (code "64") (name "Net-(R25-Pad2)") (class "Default")
      (node (ref "R25") (pin "2") (pinfunction "2_2") (pintype "passive"))
      (node (ref "R26") (pin "1") (pinfunction "1_1") (pintype "passive"))
    )
    (net (code "65") (name "Net-(RF-Pad1)") (class "Default")
      (node (ref "RF") (pin "1") (pinfunction "1_1") (pintype "passive"))
      (node (ref "RF_B") (pin "2") (pinfunction "2_2") (pintype "passive"))
    )
    (net (code "66") (name "Net-(RF_B-Pad1)") (class "Default")
      (node (ref "RF_B") (pin "1") (pinfunction "1_1") (pintype "passive"))
      (node (ref "RF_C") (pin "2") (pinfunction "2_2") (pintype "passive"))
    )
    (net (code "67") (name "Net-(RF_C-Pad1)") (class "Default")
      (node (ref "RF_C") (pin "1") (pinfunction "1_1") (pintype "passive"))
      (node (ref "RF_D") (pin "2") (pinfunction "2_2") (pintype "passive"))
    )
    (net (code "68") (name "Net-(RF_D-Pad1)") (class "Default")
      (node (ref "RF_D") (pin "1") (pinfunction "1_1") (pintype "passive"))
      (node (ref "RF_E") (pin "2") (pinfunction "2_2") (pintype "passive"))
    )
    (net (code "69") (name "Net-(RF_E-Pad1)") (class "Default")
      (node (ref "RF_E") (pin "1") (pinfunction "1_1") (pintype "passive"))
      (node (ref "RF_F") (pin "2") (pinfunction "2_2") (pintype "passive"))
    )
    (net (code "70") (name "Net-(RF_F-Pad1)") (class "Default")
      (node (ref "RF_F") (pin "1") (pinfunction "1_1") (pintype "passive"))
      (node (ref "RF_G") (pin "2") (pinfunction "2_2") (pintype "passive"))
    )
    (net (code "71") (name "Net-(U1-PA1)") (class "Default")
      (node (ref "R30") (pin "1") (pinfunction "1_1") (pintype "passive"))
      (node (ref "U1") (pin "15") (pinfunction "PA1_15") (pintype "passive"))
    )
    (net (code "72") (name "Net-(U1-PH0)") (class "Default")
      (node (ref "C17") (pin "1") (pinfunction "1_1") (pintype "passive"))
      (node (ref "U1") (pin "5") (pinfunction "PH0_5") (pintype "passive"))
      (node (ref "Y1") (pin "3") (pintype "passive"))
    )
    (net (code "73") (name "Net-(U1-PH1)") (class "Default")
      (node (ref "C16") (pin "1") (pinfunction "1_1") (pintype "passive"))
      (node (ref "U1") (pin "6") (pinfunction "PH1_6") (pintype "passive"))
      (node (ref "Y1") (pin "1") (pintype "passive"))
    )
    (net (code "74") (name "Net-(U2-DIS)") (class "Default")
      (node (ref "C12") (pin "1") (pinfunction "1_1") (pintype "passive"))
      (node (ref "C26") (pin "1") (pinfunction "1_1") (pintype "passive"))
      (node (ref "R40") (pin "2") (pinfunction "2_2") (pintype "passive"))
      (node (ref "U2") (pin "5") (pinfunction "DIS_5") (pintype "passive"))
      (node (ref "U5") (pin "5") (pinfunction "DIS_5") (pintype "passive"))
    )
    (net (code "75") (name "Net-(U2-DT)") (class "Default")
      (node (ref "C11") (pin "2") (pinfunction "2_2") (pintype "passive"))
      (node (ref "R33") (pin "2") (pinfunction "2_2") (pintype "passive"))
      (node (ref "U2") (pin "6") (pinfunction "DT_6") (pintype "passive"))
    )
    (net (code "76") (name "Net-(U2-INA)") (class "Default")
      (node (ref "C13") (pin "1") (pinfunction "1_1") (pintype "passive"))
      (node (ref "R2") (pin "2") (pinfunction "2_2") (pintype "passive"))
      (node (ref "U2") (pin "1") (pinfunction "INA_1") (pintype "passive"))
    )
    (net (code "77") (name "Net-(U2-INB)") (class "Default")
      (node (ref "C15") (pin "1") (pinfunction "1_1") (pintype "passive"))
      (node (ref "R3") (pin "2") (pinfunction "2_2") (pintype "passive"))
      (node (ref "U2") (pin "2") (pinfunction "INB_2") (pintype "passive"))
    )
    (net (code "78") (name "Net-(U2-OUTA)") (class "Default")
      (node (ref "R11") (pin "2") (pinfunction "2_2") (pintype "passive"))
      (node (ref "R6") (pin "1") (pinfunction "1_1") (pintype "passive"))
      (node (ref "U2") (pin "15") (pinfunction "OUTA_15") (pintype "passive"))
    )
    (net (code "79") (name "Net-(U2-OUTB)") (class "Default")
      (node (ref "R15") (pin "1") (pinfunction "1_1") (pintype "passive"))
      (node (ref "R31") (pin "2") (pinfunction "2_2") (pintype "passive"))
      (node (ref "U2") (pin "10") (pinfunction "OUTB_10") (pintype "passive"))
    )
    (net (code "80") (name "Net-(U5-DT)") (class "Default")
      (node (ref "C31") (pin "2") (pinfunction "2_2") (pintype "passive"))
      (node (ref "R44") (pin "2") (pinfunction "2_2") (pintype "passive"))
      (node (ref "U5") (pin "6") (pinfunction "DT_6") (pintype "passive"))
    )
    (net (code "81") (name "Net-(U5-INA)") (class "Default")
      (node (ref "C29") (pin "1") (pinfunction "1_1") (pintype "passive"))
      (node (ref "R38") (pin "2") (pinfunction "2_2") (pintype "passive"))
      (node (ref "U5") (pin "1") (pinfunction "INA_1") (pintype "passive"))
    )
    (net (code "82") (name "Net-(U5-INB)") (class "Default")
      (node (ref "C30") (pin "1") (pinfunction "1_1") (pintype "passive"))
      (node (ref "R39") (pin "2") (pinfunction "2_2") (pintype "passive"))
      (node (ref "U5") (pin "2") (pinfunction "INB_2") (pintype "passive"))
    )
    (net (code "83") (name "Net-(U5-OUTA)") (class "Default")
      (node (ref "R35") (pin "1") (pinfunction "1_1") (pintype "passive"))
      (node (ref "R36") (pin "2") (pinfunction "2_2") (pintype "passive"))
      (node (ref "U5") (pin "15") (pinfunction "OUTA_15") (pintype "passive"))
    )
    (net (code "84") (name "Net-(U5-OUTB)") (class "Default")
      (node (ref "R41") (pin "1") (pinfunction "1_1") (pintype "passive"))
      (node (ref "R42") (pin "2") (pinfunction "2_2") (pintype "passive"))
      (node (ref "U5") (pin "10") (pinfunction "OUTB_10") (pintype "passive"))
    )
    (net (code "85") (name "unconnected-(GTI_PS_A-NC-Pad8)") (class "Default")
      (node (ref "GTI_PS_A") (pin "8") (pinfunction "NC_8") (pintype "passive"))
    )
    (net (code "86") (name "unconnected-(GTI_PS_B-NC-Pad8)") (class "Default")
      (node (ref "GTI_PS_B") (pin "8") (pinfunction "NC_8") (pintype "passive"))
    )
    (net (code "87") (name "unconnected-(GT_J_SWD-Pad1)") (class "Default")
      (node (ref "GT_J_SWD") (pin "1") (pinfunction "1_1") (pintype "passive"))
    )
    (net (code "88") (name "unconnected-(GT_J_SWD-Pad5)") (class "Default")
      (node (ref "GT_J_SWD") (pin "5") (pinfunction "5_5") (pintype "passive"))
    )
    (net (code "89") (name "unconnected-(GT_J_SWD-Pad7)") (class "Default")
      (node (ref "GT_J_SWD") (pin "7") (pinfunction "7_7") (pintype "passive"))
    )
    (net (code "90") (name "unconnected-(GT_J_SWD-Pad8)") (class "Default")
      (node (ref "GT_J_SWD") (pin "8") (pinfunction "8_8") (pintype "passive"))
    )
    (net (code "91") (name "unconnected-(GT_J_SWD-Pad9)") (class "Default")
      (node (ref "GT_J_SWD") (pin "9") (pinfunction "9_9") (pintype "passive"))
    )
    (net (code "92") (name "unconnected-(GT_J_SWD-Pad10)") (class "Default")
      (node (ref "GT_J_SWD") (pin "10") (pinfunction "10_10") (pintype "passive"))
    )
    (net (code "93") (name "unconnected-(U1-PA0-Pad14)") (class "Default")
      (node (ref "U1") (pin "14") (pinfunction "PA0_14") (pintype "passive"))
    )
    (net (code "94") (name "unconnected-(U1-PA3-Pad17)") (class "Default")
      (node (ref "U1") (pin "17") (pinfunction "PA3_17") (pintype "passive"))
    )
    (net (code "95") (name "unconnected-(U1-PA4-Pad20)") (class "Default")
      (node (ref "U1") (pin "20") (pinfunction "PA4_20") (pintype "passive"))
    )
    (net (code "96") (name "unconnected-(U1-PA5-Pad21)") (class "Default")
      (node (ref "U1") (pin "21") (pinfunction "PA5_21") (pintype "passive"))
    )
    (net (code "97") (name "unconnected-(U1-PA6-Pad22)") (class "Default")
      (node (ref "U1") (pin "22") (pinfunction "PA6_22") (pintype "passive"))
    )
    (net (code "98") (name "unconnected-(U1-PA10-Pad43)") (class "Default")
      (node (ref "U1") (pin "43") (pinfunction "PA10_43") (pintype "passive"))
    )
    (net (code "99") (name "unconnected-(U1-PA12-Pad45)") (class "Default")
      (node (ref "U1") (pin "45") (pinfunction "PA12_45") (pintype "passive"))
    )
    (net (code "100") (name "unconnected-(U1-PA15-Pad50)") (class "Default")
      (node (ref "U1") (pin "50") (pinfunction "PA15_50") (pintype "passive"))
    )
    (net (code "101") (name "unconnected-(U1-PB2-Pad28)") (class "Default")
      (node (ref "U1") (pin "28") (pinfunction "PB2_28") (pintype "passive"))
    )
    (net (code "102") (name "unconnected-(U1-PB3-Pad55)") (class "Default")
      (node (ref "U1") (pin "55") (pinfunction "PB3_55") (pintype "passive"))
    )
    (net (code "103") (name "unconnected-(U1-PB4-Pad56)") (class "Default")
      (node (ref "U1") (pin "56") (pinfunction "PB4_56") (pintype "passive"))
    )
    (net (code "104") (name "unconnected-(U1-PB5-Pad57)") (class "Default")
      (node (ref "U1") (pin "57") (pinfunction "PB5_57") (pintype "passive"))
    )
    (net (code "105") (name "unconnected-(U1-PB6-Pad58)") (class "Default")
      (node (ref "U1") (pin "58") (pinfunction "PB6_58") (pintype "passive"))
    )
    (net (code "106") (name "unconnected-(U1-PB7-Pad59)") (class "Default")
      (node (ref "U1") (pin "59") (pinfunction "PB7_59") (pintype "passive"))
    )
    (net (code "107") (name "unconnected-(U1-PB8-Pad61)") (class "Default")
      (node (ref "U1") (pin "61") (pinfunction "PB8_61") (pintype "passive"))
    )
    (net (code "108") (name "unconnected-(U1-PB9-Pad62)") (class "Default")
      (node (ref "U1") (pin "62") (pinfunction "PB9_62") (pintype "passive"))
    )
    (net (code "109") (name "unconnected-(U1-PB10-Pad29)") (class "Default")
      (node (ref "U1") (pin "29") (pinfunction "PB10_29") (pintype "passive"))
    )
    (net (code "110") (name "unconnected-(U1-PB11-Pad30)") (class "Default")
      (node (ref "U1") (pin "30") (pinfunction "PB11_30") (pintype "passive"))
    )
    (net (code "111") (name "unconnected-(U1-PB13-Pad34)") (class "Default")
      (node (ref "U1") (pin "34") (pinfunction "PB13_34") (pintype "passive"))
    )
    (net (code "112") (name "unconnected-(U1-PB15-Pad36)") (class "Default")
      (node (ref "U1") (pin "36") (pinfunction "PB15_36") (pintype "passive"))
    )
    (net (code "113") (name "unconnected-(U1-PC0-Pad8)") (class "Default")
      (node (ref "U1") (pin "8") (pinfunction "PC0_8") (pintype "passive"))
    )
    (net (code "114") (name "unconnected-(U1-PC1-Pad9)") (class "Default")
      (node (ref "U1") (pin "9") (pinfunction "PC1_9") (pintype "passive"))
    )
    (net (code "115") (name "unconnected-(U1-PC3-Pad11)") (class "Default")
      (node (ref "U1") (pin "11") (pinfunction "PC3_11") (pintype "passive"))
    )
    (net (code "116") (name "unconnected-(U1-PC4-Pad24)") (class "Default")
      (node (ref "U1") (pin "24") (pinfunction "PC4_24") (pintype "passive"))
    )
    (net (code "117") (name "unconnected-(U1-PC5-Pad25)") (class "Default")
      (node (ref "U1") (pin "25") (pinfunction "PC5_25") (pintype "passive"))
    )
    (net (code "118") (name "unconnected-(U1-PC6-Pad37)") (class "Default")
      (node (ref "U1") (pin "37") (pinfunction "PC6_37") (pintype "passive"))
    )
    (net (code "119") (name "unconnected-(U1-PC7-Pad38)") (class "Default")
      (node (ref "U1") (pin "38") (pinfunction "PC7_38") (pintype "passive"))
    )
    (net (code "120") (name "unconnected-(U1-PC8-Pad39)") (class "Default")
      (node (ref "U1") (pin "39") (pinfunction "PC8_39") (pintype "passive"))
    )
    (net (code "121") (name "unconnected-(U1-PC9-Pad40)") (class "Default")
      (node (ref "U1") (pin "40") (pinfunction "PC9_40") (pintype "passive"))
    )
    (net (code "122") (name "unconnected-(U1-PC10-Pad51)") (class "Default")
      (node (ref "U1") (pin "51") (pinfunction "PC10_51") (pintype "passive"))
    )
    (net (code "123") (name "unconnected-(U1-PC11-Pad52)") (class "Default")
      (node (ref "U1") (pin "52") (pinfunction "PC11_52") (pintype "passive"))
    )
    (net (code "124") (name "unconnected-(U1-PC12-Pad53)") (class "Default")
      (node (ref "U1") (pin "53") (pinfunction "PC12_53") (pintype "passive"))
    )
    (net (code "125") (name "unconnected-(U1-PC13-Pad2)") (class "Default")
      (node (ref "U1") (pin "2") (pinfunction "PC13_2") (pintype "passive"))
    )
    (net (code "126") (name "unconnected-(U1-PC14-Pad3)") (class "Default")
      (node (ref "U1") (pin "3") (pinfunction "PC14_3") (pintype "passive"))
    )
    (net (code "127") (name "unconnected-(U1-PC15-Pad4)") (class "Default")
      (node (ref "U1") (pin "4") (pinfunction "PC15_4") (pintype "passive"))
    )
    (net (code "128") (name "unconnected-(U1-PD2-Pad54)") (class "Default")
      (node (ref "U1") (pin "54") (pinfunction "PD2_54") (pintype "passive"))
    )
    (net (code "129") (name "unconnected-(Y1-GND-Pad2)") (class "Default")
      (node (ref "Y1") (pin "2") (pinfunction "GND_2") (pintype "passive"))
    )
    (net (code "130") (name "unconnected-(Y1-GND-Pad4)") (class "Default")
      (node (ref "Y1") (pin "4") (pinfunction "GND_4") (pintype "passive"))
    )
  )
)
